# LaserCutter.net
KiCad netlist of a schematic drawn in EAGLE
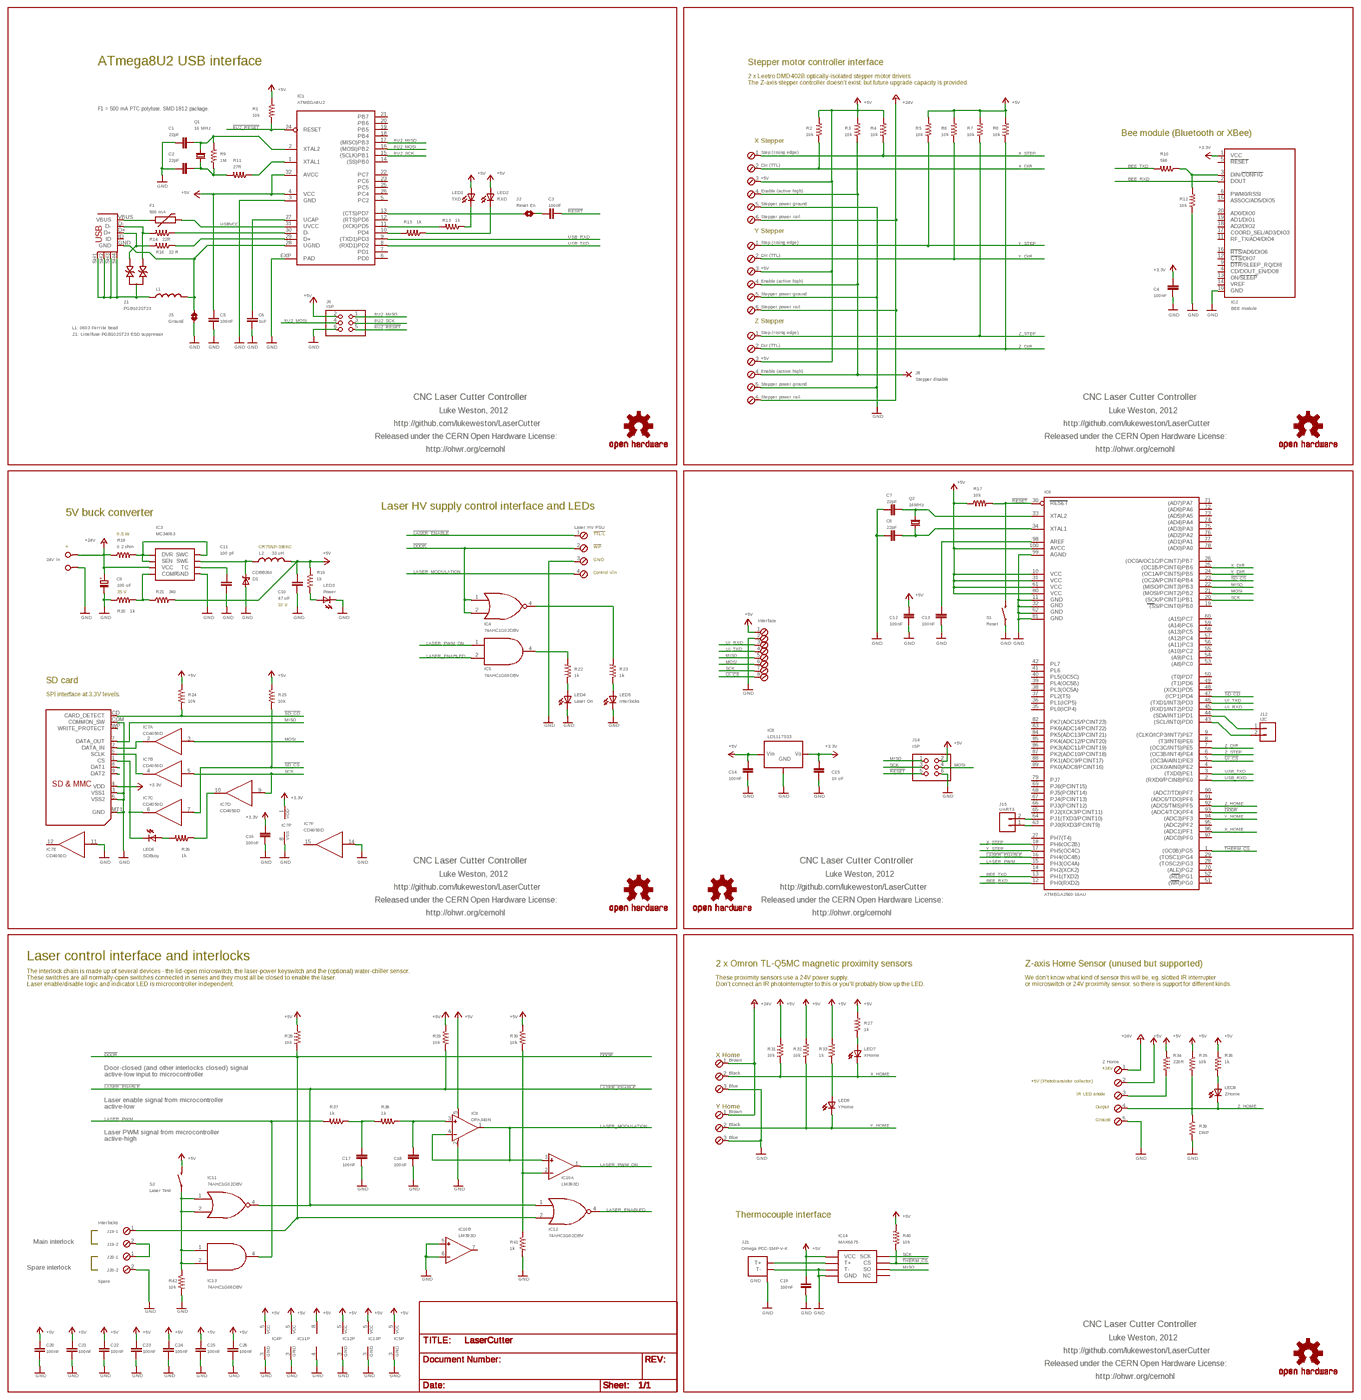
[diagram p0: schematic, sheet 1, overview]
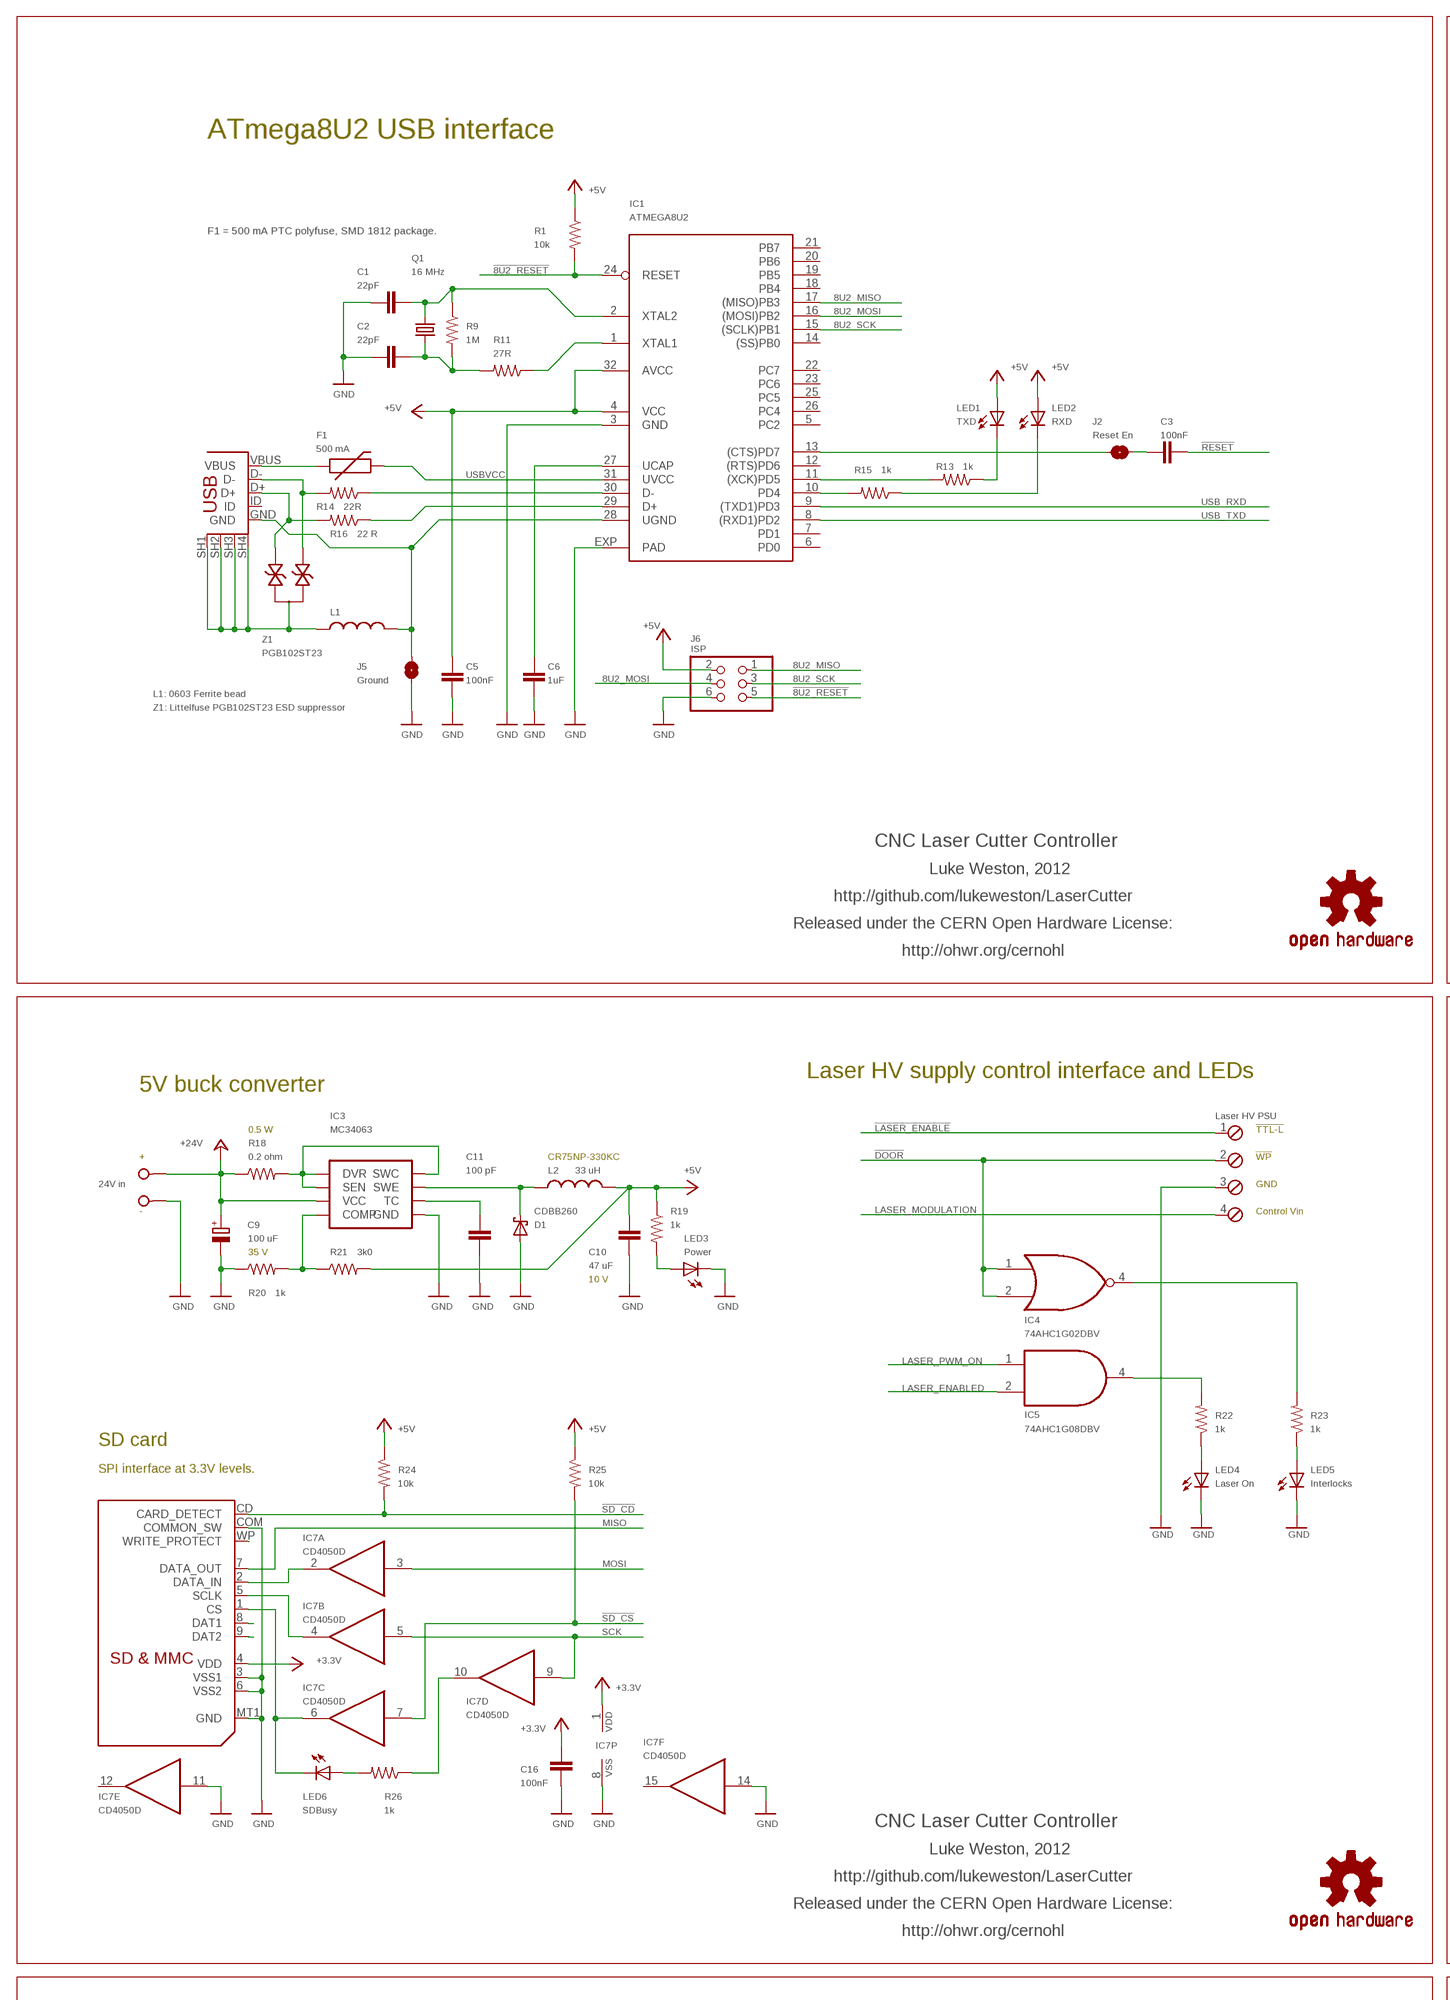
[diagram p1: schematic, sheet 1, part 1 of 4]
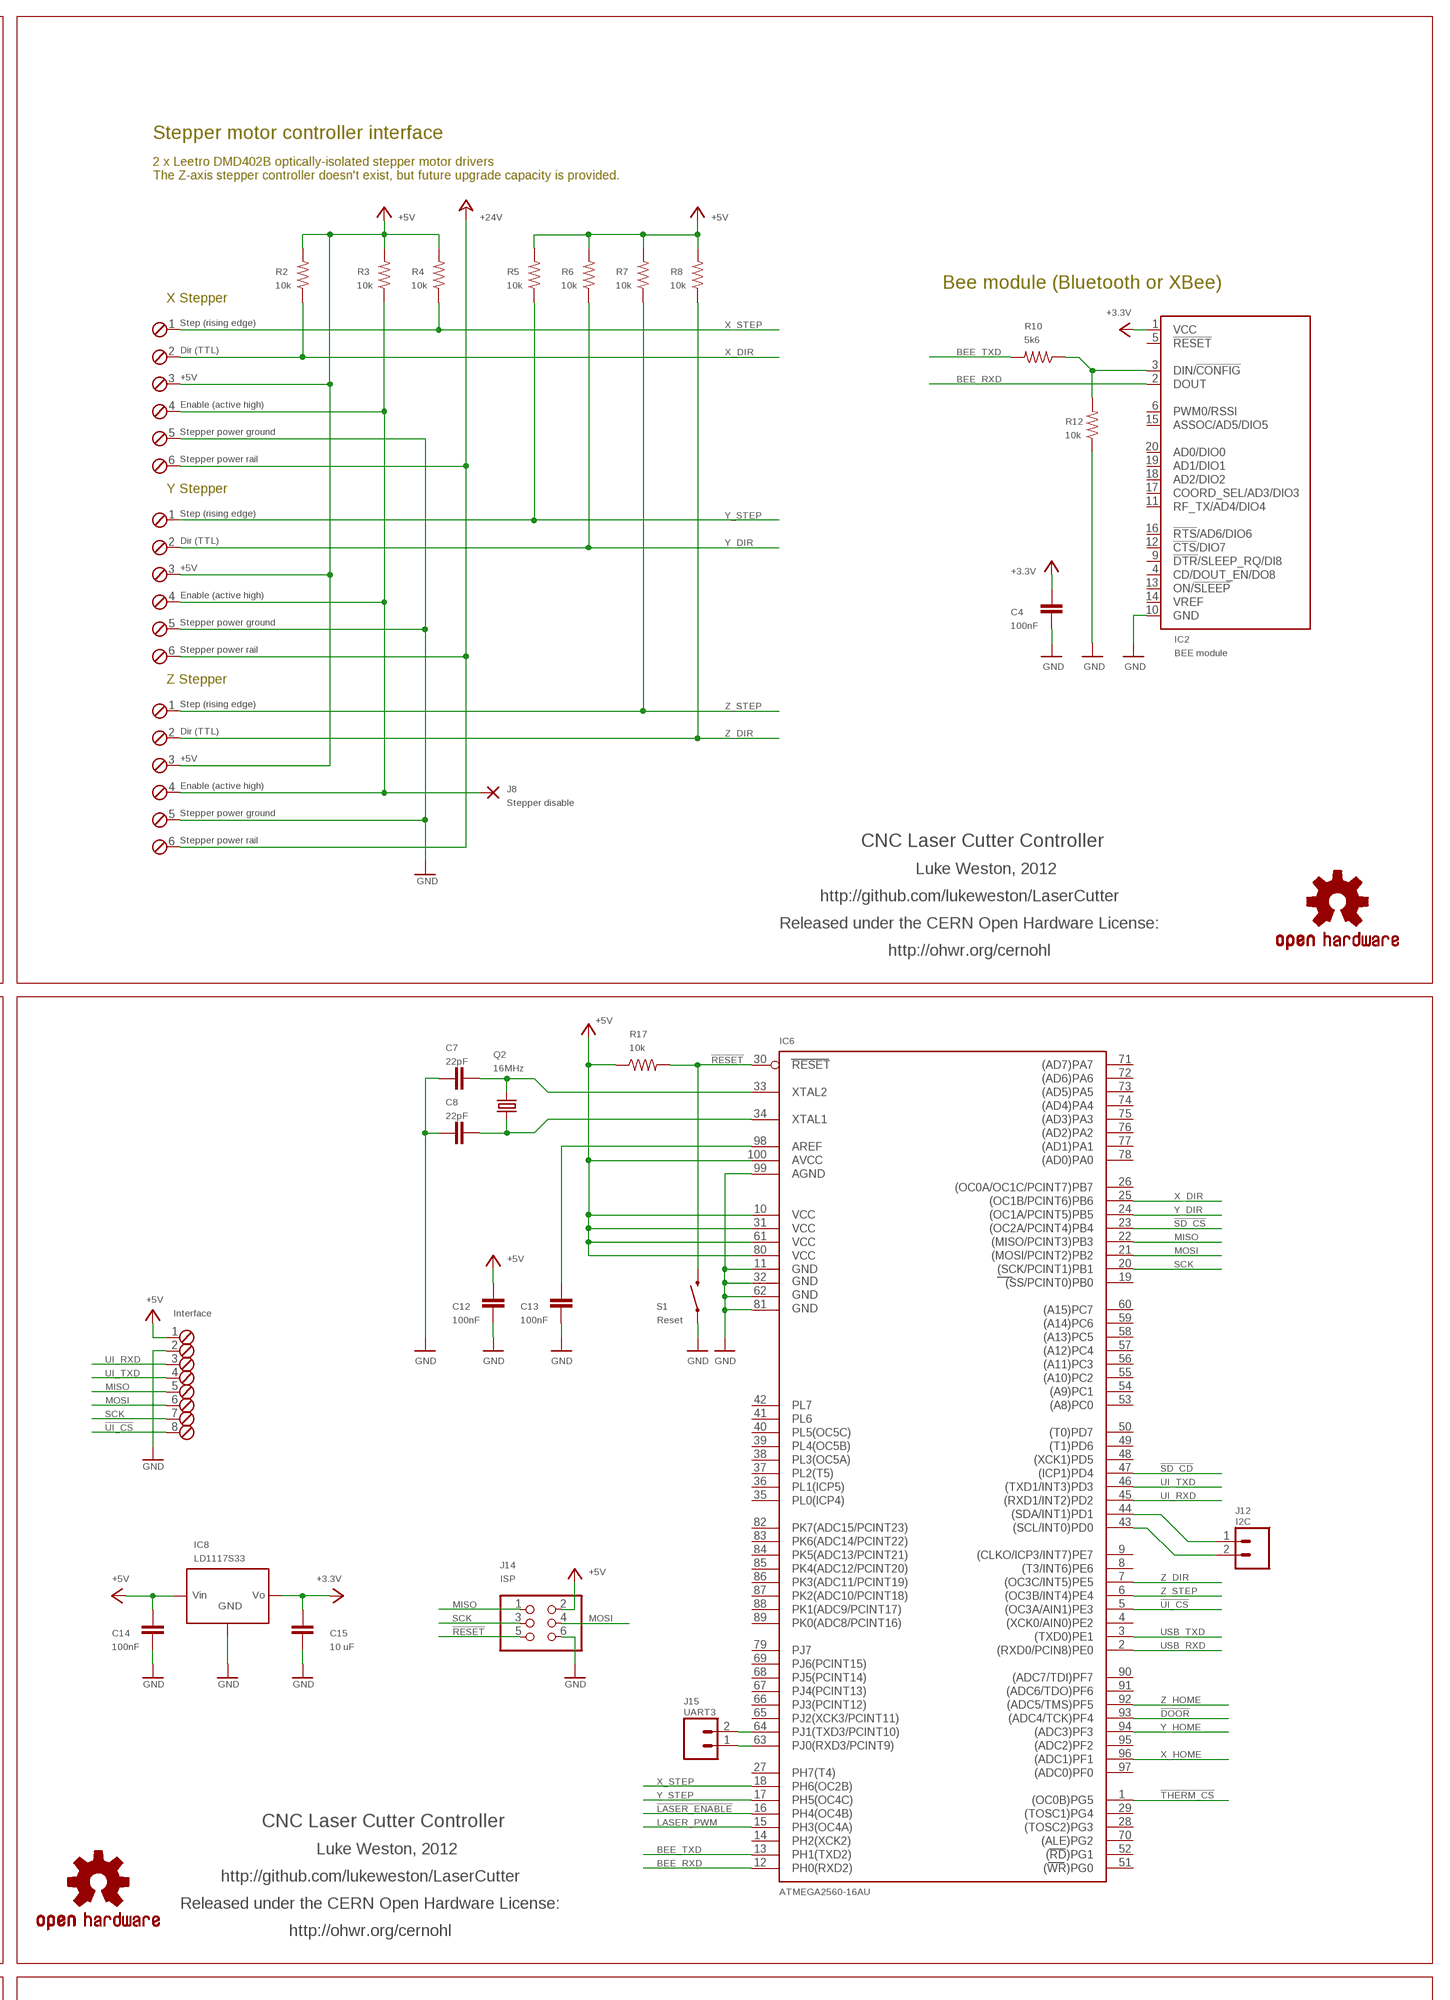
[diagram p2: schematic, sheet 1, part 2 of 4]
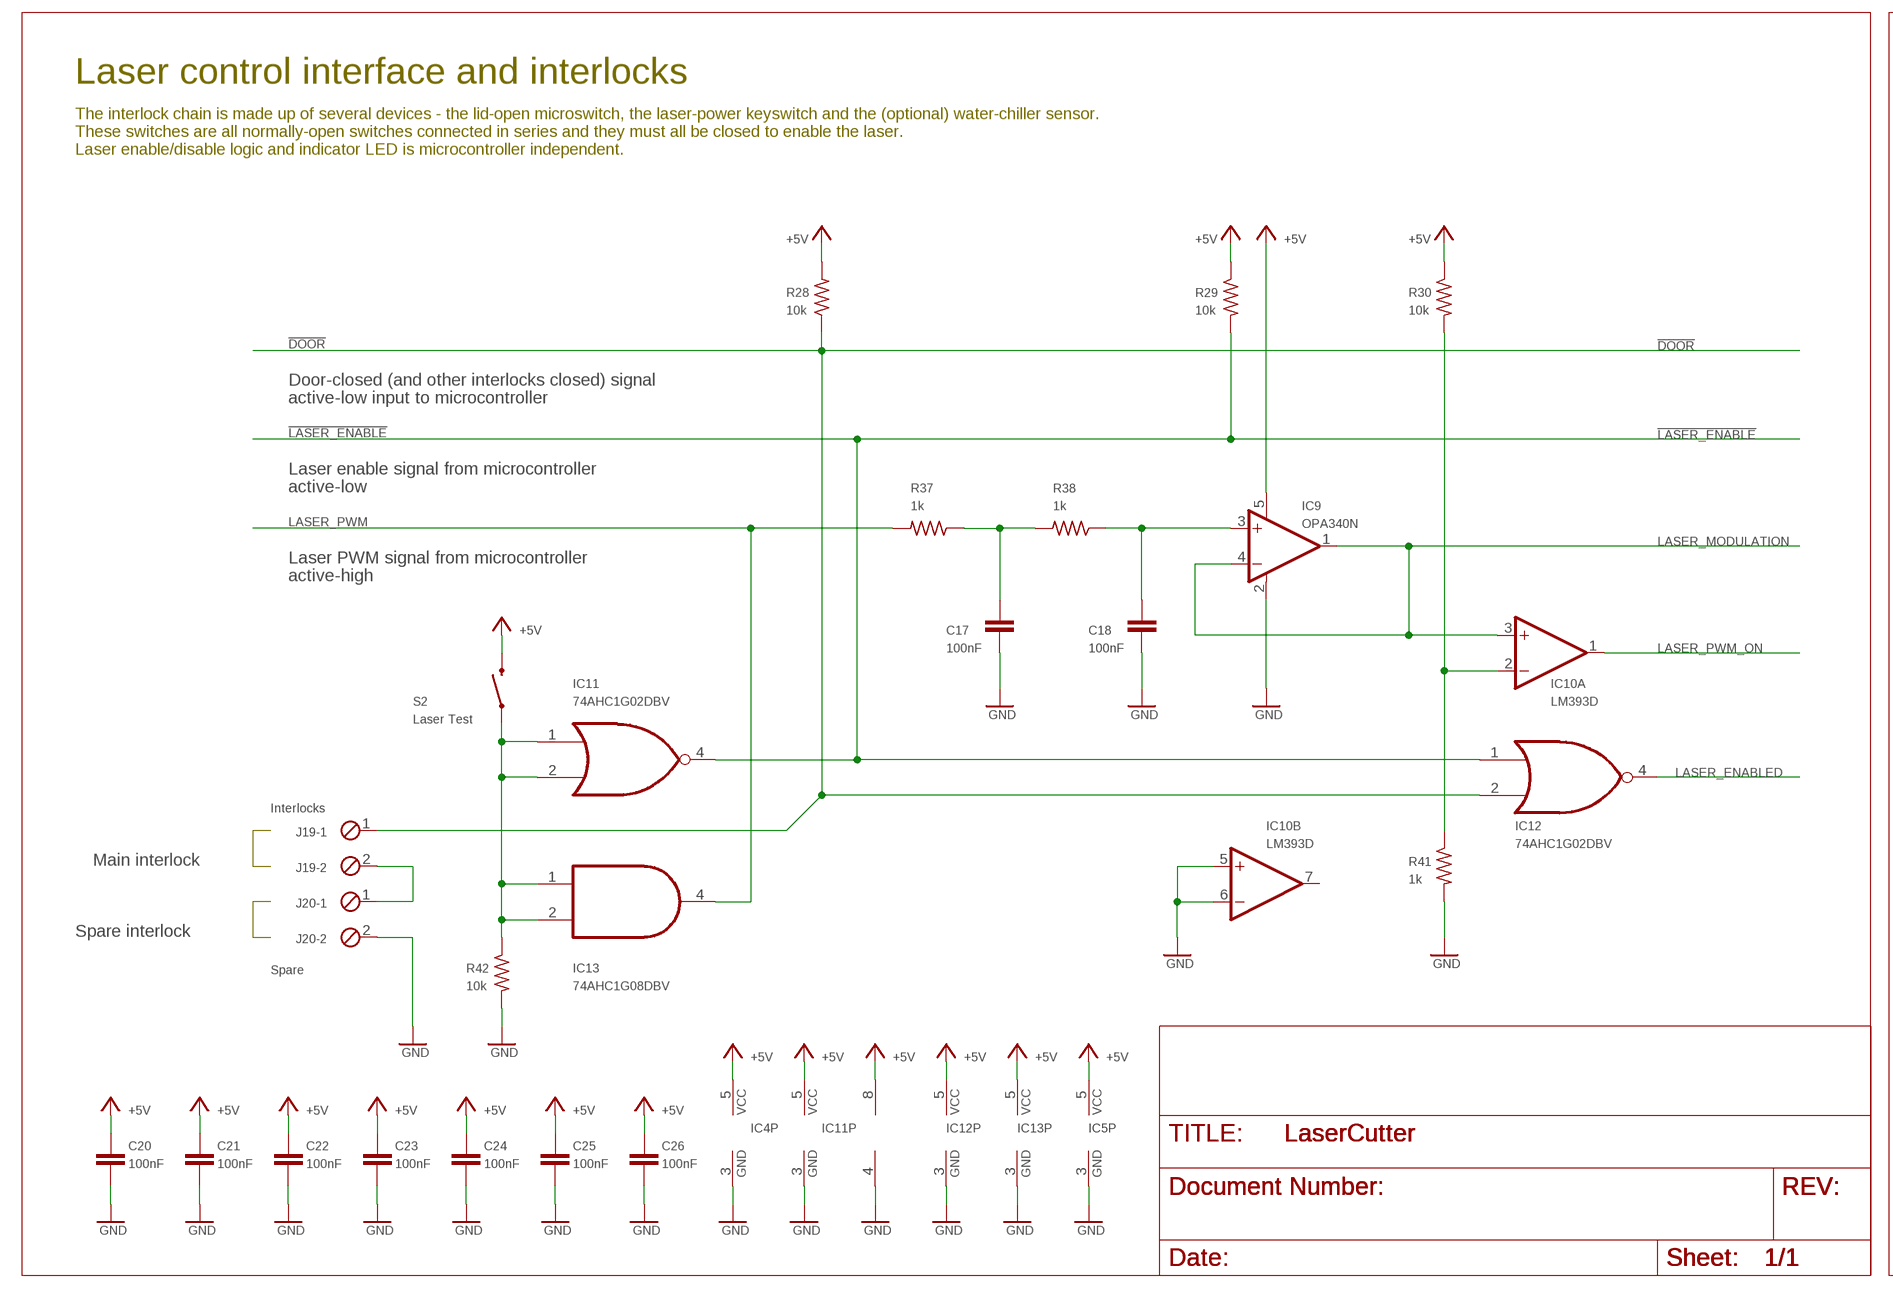
[diagram p3: schematic, sheet 1, part 3 of 4]
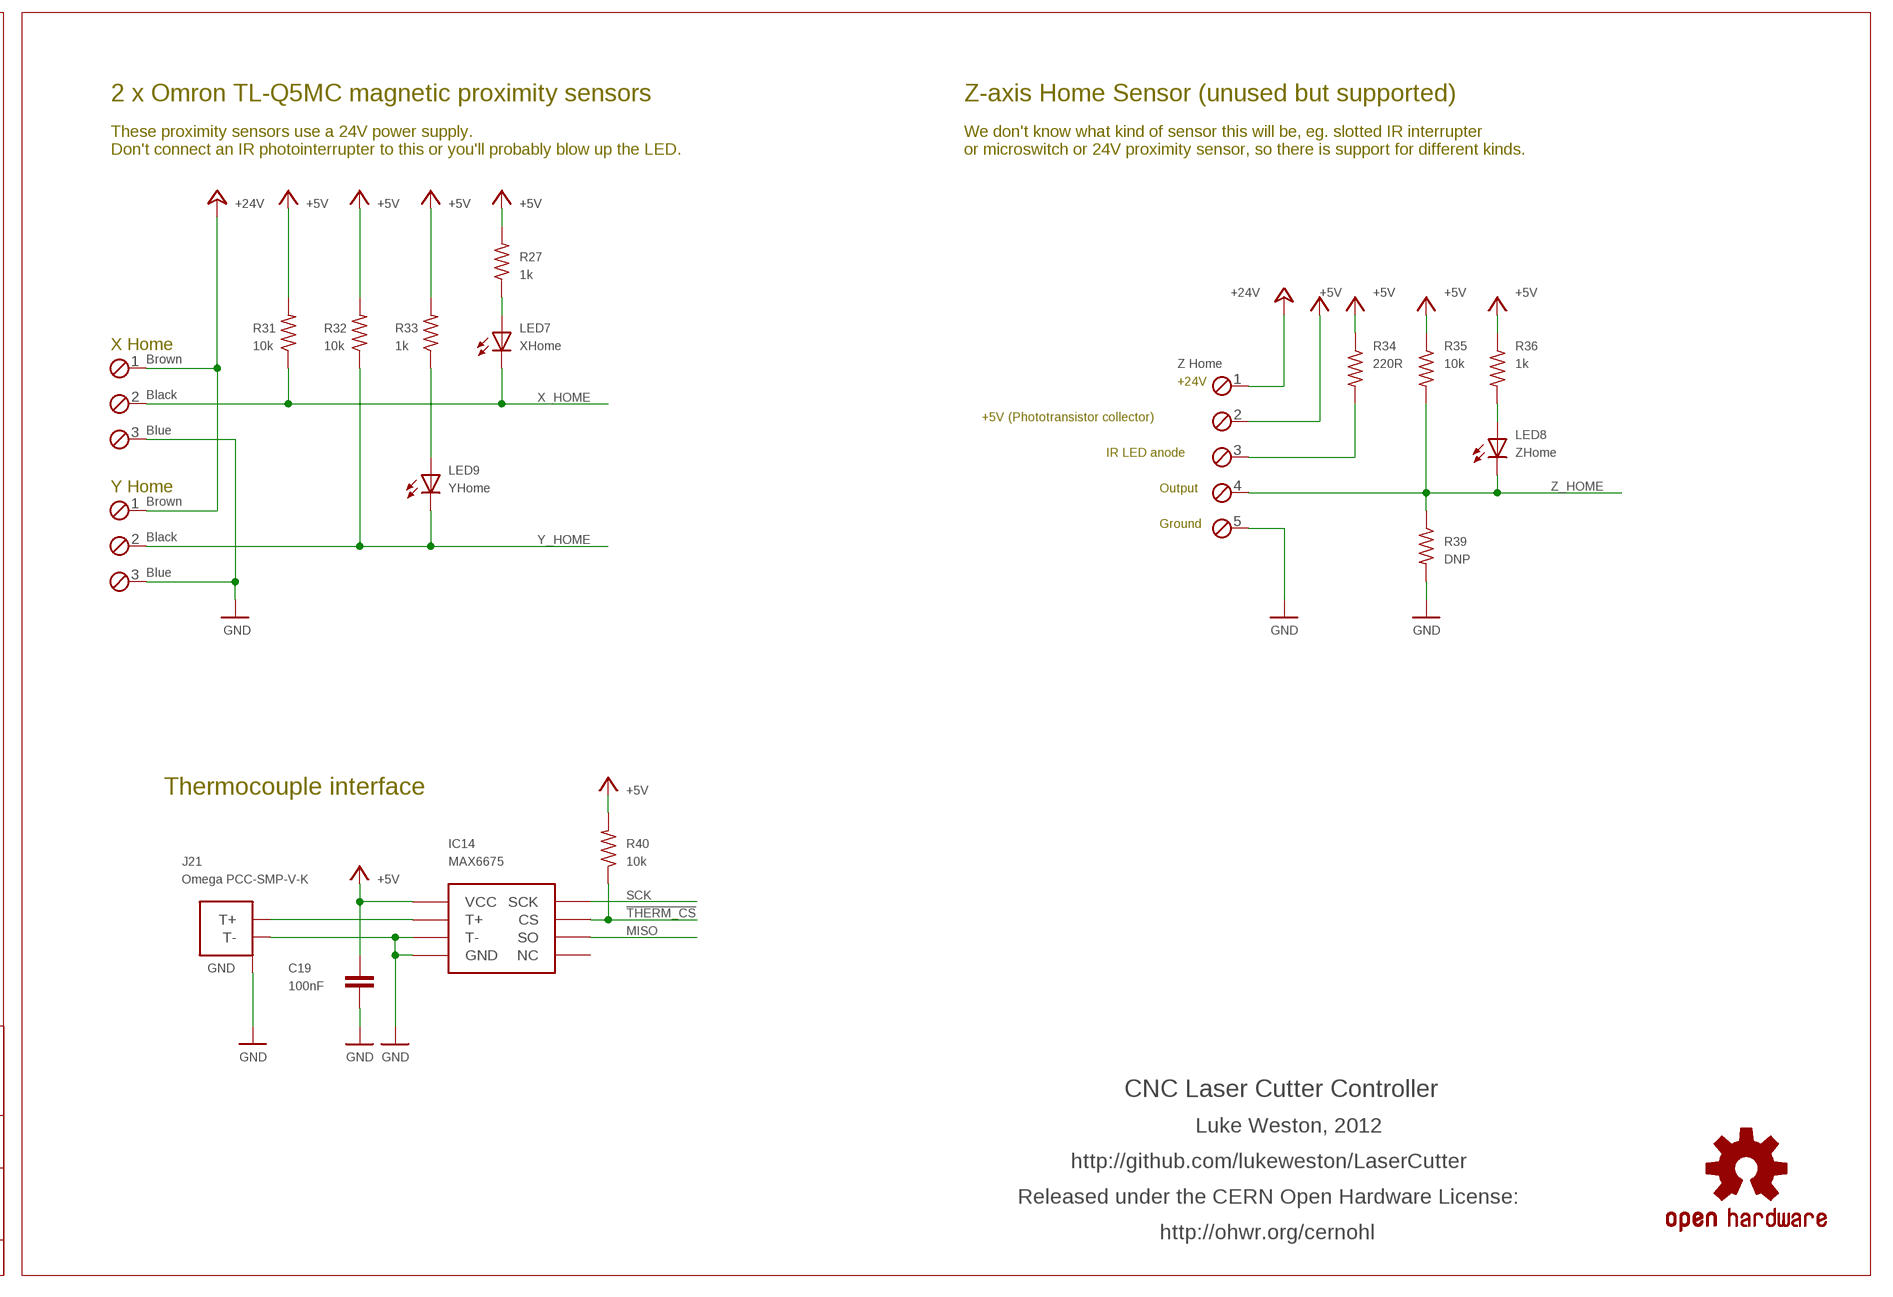
[diagram p4: schematic, sheet 1, part 4 of 4]

(export (version "E")
  (design (tool "Eeschema 10.0.6"))
  (components
    (comp (ref "$1")
      (value "OSHW-LOGOS")
      (footprint "eagle-import:OSHW-LOGO-S")
      (libsource (lib "eagle-import") (part "OSHW-LOGOS"))
    )
    (comp (ref "C1")
      (value "22pF")
      (footprint "eagle-import:0805-LARGE")
      (libsource (lib "eagle-import") (part "CAP0805-LARGE"))
    )
    (comp (ref "C2")
      (value "22pF")
      (footprint "eagle-import:0805-LARGE")
      (libsource (lib "eagle-import") (part "CAP0805-LARGE"))
    )
    (comp (ref "C3")
      (value "100nF")
      (footprint "eagle-import:0805-LARGE")
      (libsource (lib "eagle-import") (part "CAP0805-LARGE"))
    )
    (comp (ref "C4")
      (value "100nF")
      (footprint "eagle-import:C0805K")
      (libsource (lib "eagle-import") (part "C-EUC0805K"))
    )
    (comp (ref "C5")
      (value "100nF")
      (footprint "eagle-import:0805-LARGE")
      (libsource (lib "eagle-import") (part "CAP0805-LARGE"))
    )
    (comp (ref "C6")
      (value "1uF")
      (footprint "eagle-import:0805-LARGE")
      (libsource (lib "eagle-import") (part "freetronics-master-v1_CAP0805-LARGE"))
    )
    (comp (ref "C7")
      (value "22pF")
      (footprint "eagle-import:C0805K")
      (libsource (lib "eagle-import") (part "C-EUC0805K"))
    )
    (comp (ref "C8")
      (value "22pF")
      (footprint "eagle-import:C0805K")
      (libsource (lib "eagle-import") (part "C-EUC0805K"))
    )
    (comp (ref "C9")
      (value "100 uF")
      (footprint "eagle-import:E2,5-6")
      (libsource (lib "eagle-import") (part "CPOL-EUE2.5-6"))
    )
    (comp (ref "C10")
      (value "47 uF")
      (footprint "eagle-import:C1210")
      (libsource (lib "eagle-import") (part "C-EUC1210"))
    )
    (comp (ref "C11")
      (value "100 pF")
      (footprint "eagle-import:0805-LARGE")
      (libsource (lib "eagle-import") (part "freetronics-master-v1_CAP0805-LARGE"))
    )
    (comp (ref "C12")
      (value "100nF")
      (footprint "eagle-import:C0805K")
      (libsource (lib "eagle-import") (part "C-EUC0805K"))
    )
    (comp (ref "C13")
      (value "100nF")
      (footprint "eagle-import:C0805K")
      (libsource (lib "eagle-import") (part "C-EUC0805K"))
    )
    (comp (ref "C14")
      (value "100nF")
      (footprint "eagle-import:C0805K")
      (libsource (lib "eagle-import") (part "C-EUC0805K"))
    )
    (comp (ref "C15")
      (value "10 uF")
      (footprint "eagle-import:C0805K")
      (libsource (lib "eagle-import") (part "C-EUC0805K"))
    )
    (comp (ref "C16")
      (value "100nF")
      (footprint "eagle-import:C0805K")
      (libsource (lib "eagle-import") (part "C-EUC0805K"))
    )
    (comp (ref "C17")
      (value "100nF")
      (footprint "eagle-import:C0805K")
      (libsource (lib "eagle-import") (part "C-EUC0805K"))
    )
    (comp (ref "C18")
      (value "100nF")
      (footprint "eagle-import:C0805K")
      (libsource (lib "eagle-import") (part "C-EUC0805K"))
    )
    (comp (ref "C19")
      (value "100nF")
      (footprint "eagle-import:C0805K")
      (libsource (lib "eagle-import") (part "C-EUC0805K"))
    )
    (comp (ref "C20")
      (value "100nF")
      (footprint "eagle-import:C0805K")
      (libsource (lib "eagle-import") (part "C-EUC0805K"))
    )
    (comp (ref "C21")
      (value "100nF")
      (footprint "eagle-import:C0805K")
      (libsource (lib "eagle-import") (part "C-EUC0805K"))
    )
    (comp (ref "C22")
      (value "100nF")
      (footprint "eagle-import:C0805K")
      (libsource (lib "eagle-import") (part "C-EUC0805K"))
    )
    (comp (ref "C23")
      (value "100nF")
      (footprint "eagle-import:C0805K")
      (libsource (lib "eagle-import") (part "C-EUC0805K"))
    )
    (comp (ref "C24")
      (value "100nF")
      (footprint "eagle-import:C0805K")
      (libsource (lib "eagle-import") (part "C-EUC0805K"))
    )
    (comp (ref "C25")
      (value "100nF")
      (footprint "eagle-import:C0805K")
      (libsource (lib "eagle-import") (part "C-EUC0805K"))
    )
    (comp (ref "C26")
      (value "100nF")
      (footprint "eagle-import:C0805K")
      (libsource (lib "eagle-import") (part "C-EUC0805K"))
    )
    (comp (ref "D1")
      (value "CDBB260")
      (footprint "eagle-import:SMB")
      (libsource (lib "eagle-import") (part "MBRS130LT3"))
    )
    (comp (ref "F1")
      (value "500 mA")
      (footprint "eagle-import:1812")
      (libsource (lib "eagle-import") (part "PTC1812"))
    )
    (comp (ref "IC1")
      (value "ATMEGA8U2")
      (footprint "eagle-import:ATMEL_QFN32")
      (libsource (lib "eagle-import") (part "ATMEL_ATMEGA8U2-MUQFN"))
    )
    (comp (ref "IC2")
      (value "BEE module")
      (footprint "eagle-import:XBEE-PRO")
      (libsource (lib "eagle-import") (part "XBEE"))
    )
    (comp (ref "IC3")
      (value "MC34063")
      (footprint "eagle-import:SO08")
      (libsource (lib "eagle-import") (part "MC34063SMD"))
    )
    (comp (ref "IC4")
      (value "74AHC1G02DBV")
      (footprint "eagle-import:SOT23-5")
      (libsource (lib "eagle-import") (part "741G02DBVAHC"))
    )
    (comp (ref "IC5")
      (value "74AHC1G08DBV")
      (footprint "eagle-import:SOT23-5")
      (libsource (lib "eagle-import") (part "741G08DBVAHC"))
    )
    (comp (ref "IC6")
      (value "ATMEGA2560-16AU")
      (footprint "eagle-import:TQFP100")
      (libsource (lib "eagle-import") (part "ATMEGAAU1280-16"))
    )
    (comp (ref "IC7")
      (value "CD4050D")
      (footprint "eagle-import:SO16")
      (libsource (lib "eagle-import") (part "4050D"))
    )
    (comp (ref "IC8")
      (value "LD1117S33")
      (footprint "eagle-import:SOT223")
      (fields (field (name "MPN") "REG1117"))
      (libsource (lib "eagle-import") (part "REG1117"))
    )
    (comp (ref "IC9")
      (value "OPA340N")
      (footprint "eagle-import:SOT23-5")
      (fields (field (name "MPN") "OPA340NA/3KG4"))
      (libsource (lib "eagle-import") (part "OPA340N"))
    )
    (comp (ref "IC10")
      (value "LM393D")
      (footprint "eagle-import:SO08")
      (libsource (lib "eagle-import") (part "LM393D"))
    )
    (comp (ref "IC11")
      (value "74AHC1G02DBV")
      (footprint "eagle-import:SOT23-5")
      (libsource (lib "eagle-import") (part "741G02DBVAHC"))
    )
    (comp (ref "IC12")
      (value "74AHC1G02DBV")
      (footprint "eagle-import:SOT23-5")
      (libsource (lib "eagle-import") (part "741G02DBVAHC"))
    )
    (comp (ref "IC13")
      (value "74AHC1G08DBV")
      (footprint "eagle-import:SOT23-5")
      (libsource (lib "eagle-import") (part "741G08DBVAHC"))
    )
    (comp (ref "IC14")
      (value "MAX6675")
      (footprint "eagle-import:SOIC8-2")
      (libsource (lib "eagle-import") (part "MAX6675"))
    )
    (comp (ref "J1")
      (value "X Stepper")
      (footprint "eagle-import:6POL254")
      (libsource (lib "eagle-import") (part "MPT6"))
    )
    (comp (ref "J2")
      (value "Reset En")
      (footprint "eagle-import:SJ")
      (libsource (lib "eagle-import") (part "SJ"))
    )
    (comp (ref "J3")
      (value "USB")
      (footprint "eagle-import:USB-MINIB-FT")
      (libsource (lib "eagle-import") (part "USB-FT"))
    )
    (comp (ref "J4")
      (value "Y Stepper")
      (footprint "eagle-import:6POL254")
      (libsource (lib "eagle-import") (part "MPT6"))
    )
    (comp (ref "J5")
      (value "Ground")
      (footprint "eagle-import:SJ")
      (libsource (lib "eagle-import") (part "SJ"))
    )
    (comp (ref "J6")
      (value "ISP")
      (footprint "eagle-import:2X03")
      (libsource (lib "eagle-import") (part "PINHD-2X3"))
    )
    (comp (ref "J7")
      (value "Z Stepper")
      (footprint "eagle-import:6POL254")
      (libsource (lib "eagle-import") (part "MPT6"))
    )
    (comp (ref "J8")
      (value "Stepper disable")
      (footprint "eagle-import:1,6_0,8")
      (libsource (lib "eagle-import") (part "1,6/0,8"))
    )
    (comp (ref "J9")
      (value "Laser HV PSU")
      (footprint "eagle-import:4POL254")
      (libsource (lib "eagle-import") (part "MPT4"))
    )
    (comp (ref "J10")
      (value "24V in")
      (footprint "eagle-import:W237-132")
      (libsource (lib "eagle-import") (part "W237-02P"))
    )
    (comp (ref "J11")
      (value "Interface")
      (footprint "eagle-import:8POL254")
      (libsource (lib "eagle-import") (part "MPT8"))
    )
    (comp (ref "J12")
      (value "I2C")
      (footprint "eagle-import:1X02")
      (libsource (lib "eagle-import") (part "M02PTH"))
    )
    (comp (ref "J13")
      (value "SDMMC18650")
      (footprint "eagle-import:SDCARD")
      (libsource (lib "eagle-import") (part "SDMMC18650"))
    )
    (comp (ref "J14")
      (value "ISP")
      (footprint "eagle-import:2X03")
      (libsource (lib "eagle-import") (part "PINHD-2X3"))
    )
    (comp (ref "J15")
      (value "UART3")
      (footprint "eagle-import:1X02")
      (libsource (lib "eagle-import") (part "M02PTH"))
    )
    (comp (ref "J16")
      (value "X Home")
      (footprint "eagle-import:3POL254")
      (libsource (lib "eagle-import") (part "MPT3"))
    )
    (comp (ref "J17")
      (value "Z Home")
      (footprint "eagle-import:5POL254")
      (libsource (lib "eagle-import") (part "MPT5"))
    )
    (comp (ref "J18")
      (value "Y Home")
      (footprint "eagle-import:3POL254")
      (libsource (lib "eagle-import") (part "MPT3"))
    )
    (comp (ref "J19")
      (value "Interlocks")
      (footprint "eagle-import:2POL254")
      (libsource (lib "eagle-import") (part "MPT2"))
    )
    (comp (ref "J20")
      (value "Spare")
      (footprint "eagle-import:2POL254")
      (libsource (lib "eagle-import") (part "MPT2"))
    )
    (comp (ref "J21")
      (value "Omega PCC-SMP-V-K")
      (footprint "eagle-import:PCC-SMP-V")
      (libsource (lib "eagle-import") (part "PCC-SMP-V"))
    )
    (comp (ref "L1")
      (value "L1: 0603 Ferrite bead")
      (footprint "eagle-import:0603")
      (libsource (lib "eagle-import") (part "freetronics-master-v1_INDUCTOR0603"))
    )
    (comp (ref "L2")
      (value "33 uH")
      (footprint "eagle-import:CR75")
      (libsource (lib "eagle-import") (part "INDUCTORCR75"))
    )
    (comp (ref "LED1")
      (value "TXD")
      (footprint "eagle-import:LED-0805")
      (libsource (lib "eagle-import") (part "LED0805"))
    )
    (comp (ref "LED2")
      (value "RXD")
      (footprint "eagle-import:LED-0805")
      (libsource (lib "eagle-import") (part "LED0805"))
    )
    (comp (ref "LED3")
      (value "Power")
      (footprint "eagle-import:LED-0805-LARGE")
      (libsource (lib "eagle-import") (part "LED0805-LARGE"))
    )
    (comp (ref "LED4")
      (value "Laser On")
      (footprint "eagle-import:LED-0805-LARGE")
      (libsource (lib "eagle-import") (part "LED0805-LARGE"))
    )
    (comp (ref "LED5")
      (value "Interlocks")
      (footprint "eagle-import:LED-0805-LARGE")
      (libsource (lib "eagle-import") (part "LED0805-LARGE"))
    )
    (comp (ref "LED6")
      (value "SDBusy")
      (footprint "eagle-import:LED-0805-LARGE")
      (libsource (lib "eagle-import") (part "LED0805-LARGE"))
    )
    (comp (ref "LED7")
      (value "XHome")
      (footprint "eagle-import:LED-0805-LARGE")
      (libsource (lib "eagle-import") (part "LED0805-LARGE"))
    )
    (comp (ref "LED8")
      (value "ZHome")
      (footprint "eagle-import:LED-0805-LARGE")
      (libsource (lib "eagle-import") (part "LED0805-LARGE"))
    )
    (comp (ref "LED9")
      (value "YHome")
      (footprint "eagle-import:LED-0805-LARGE")
      (libsource (lib "eagle-import") (part "LED0805-LARGE"))
    )
    (comp (ref "Q1")
      (value "16 MHz")
      (footprint "eagle-import:CRYSTAL-SMD-5X3")
      (libsource (lib "eagle-import") (part "CRYSTAL5X3"))
    )
    (comp (ref "Q2")
      (value "16MHz")
      (footprint "eagle-import:CRYSTAL-SMD-5X3")
      (libsource (lib "eagle-import") (part "CRYSTAL5X3"))
    )
    (comp (ref "R1")
      (value "10k")
      (footprint "eagle-import:R0805")
      (libsource (lib "eagle-import") (part "R-US_R0805"))
    )
    (comp (ref "R2")
      (value "10k")
      (footprint "eagle-import:M0805")
      (libsource (lib "eagle-import") (part "resistor_R-US_M0805"))
    )
    (comp (ref "R3")
      (value "10k")
      (footprint "eagle-import:M0805")
      (libsource (lib "eagle-import") (part "resistor_R-US_M0805"))
    )
    (comp (ref "R4")
      (value "10k")
      (footprint "eagle-import:M0805")
      (libsource (lib "eagle-import") (part "resistor_R-US_M0805"))
    )
    (comp (ref "R5")
      (value "10k")
      (footprint "eagle-import:M0805")
      (libsource (lib "eagle-import") (part "resistor_R-US_M0805"))
    )
    (comp (ref "R6")
      (value "10k")
      (footprint "eagle-import:M0805")
      (libsource (lib "eagle-import") (part "resistor_R-US_M0805"))
    )
    (comp (ref "R7")
      (value "10k")
      (footprint "eagle-import:M0805")
      (libsource (lib "eagle-import") (part "resistor_R-US_M0805"))
    )
    (comp (ref "R8")
      (value "10k")
      (footprint "eagle-import:M0805")
      (libsource (lib "eagle-import") (part "resistor_R-US_M0805"))
    )
    (comp (ref "R9")
      (value "1M")
      (footprint "eagle-import:R0805")
      (libsource (lib "eagle-import") (part "R-US_R0805"))
    )
    (comp (ref "R10")
      (value "5k6")
      (footprint "eagle-import:M0805")
      (libsource (lib "eagle-import") (part "resistor_R-US_M0805"))
    )
    (comp (ref "R11")
      (value "27R")
      (footprint "eagle-import:R0805")
      (libsource (lib "eagle-import") (part "R-US_R0805"))
    )
    (comp (ref "R12")
      (value "10k")
      (footprint "eagle-import:M0805")
      (libsource (lib "eagle-import") (part "resistor_R-US_M0805"))
    )
    (comp (ref "R13")
      (value "1k")
      (footprint "eagle-import:R0805")
      (libsource (lib "eagle-import") (part "R-US_R0805"))
    )
    (comp (ref "R14")
      (value "22R")
      (footprint "eagle-import:R0805")
      (libsource (lib "eagle-import") (part "R-US_R0805"))
    )
    (comp (ref "R15")
      (value "1k")
      (footprint "eagle-import:R0805")
      (libsource (lib "eagle-import") (part "R-US_R0805"))
    )
    (comp (ref "R16")
      (value "22 R")
      (footprint "eagle-import:R0805")
      (libsource (lib "eagle-import") (part "R-US_R0805"))
    )
    (comp (ref "R17")
      (value "10k")
      (footprint "eagle-import:R0805")
      (libsource (lib "eagle-import") (part "R-US_R0805"))
    )
    (comp (ref "R18")
      (value "0.2 ohm")
      (footprint "eagle-import:R1210")
      (libsource (lib "eagle-import") (part "R-US_R1210"))
    )
    (comp (ref "R19")
      (value "1k")
      (footprint "eagle-import:R0805")
      (libsource (lib "eagle-import") (part "R-US_R0805"))
    )
    (comp (ref "R20")
      (value "1k")
      (footprint "eagle-import:R0805")
      (libsource (lib "eagle-import") (part "R-US_R0805"))
    )
    (comp (ref "R21")
      (value "3k0")
      (footprint "eagle-import:R0805")
      (libsource (lib "eagle-import") (part "R-US_R0805"))
    )
    (comp (ref "R22")
      (value "1k")
      (footprint "eagle-import:M0805")
      (libsource (lib "eagle-import") (part "resistor_R-US_M0805"))
    )
    (comp (ref "R23")
      (value "1k")
      (footprint "eagle-import:M0805")
      (libsource (lib "eagle-import") (part "resistor_R-US_M0805"))
    )
    (comp (ref "R24")
      (value "10k")
      (footprint "eagle-import:M0805")
      (libsource (lib "eagle-import") (part "resistor_R-US_M0805"))
    )
    (comp (ref "R25")
      (value "10k")
      (footprint "eagle-import:M0805")
      (libsource (lib "eagle-import") (part "resistor_R-US_M0805"))
    )
    (comp (ref "R26")
      (value "1k")
      (footprint "eagle-import:R0805")
      (libsource (lib "eagle-import") (part "R-US_R0805"))
    )
    (comp (ref "R27")
      (value "1k")
      (footprint "eagle-import:M0805")
      (libsource (lib "eagle-import") (part "resistor_R-US_M0805"))
    )
    (comp (ref "R28")
      (value "10k")
      (footprint "eagle-import:R0805")
      (libsource (lib "eagle-import") (part "resistor_R-US_R0805"))
    )
    (comp (ref "R29")
      (value "10k")
      (footprint "eagle-import:M0805")
      (libsource (lib "eagle-import") (part "resistor_R-US_M0805"))
    )
    (comp (ref "R30")
      (value "10k")
      (footprint "eagle-import:M0805")
      (libsource (lib "eagle-import") (part "resistor_R-US_M0805"))
    )
    (comp (ref "R31")
      (value "10k")
      (footprint "eagle-import:M0805")
      (libsource (lib "eagle-import") (part "resistor_R-US_M0805"))
    )
    (comp (ref "R32")
      (value "10k")
      (footprint "eagle-import:M0805")
      (libsource (lib "eagle-import") (part "resistor_R-US_M0805"))
    )
    (comp (ref "R33")
      (value "1k")
      (footprint "eagle-import:M0805")
      (libsource (lib "eagle-import") (part "resistor_R-US_M0805"))
    )
    (comp (ref "R34")
      (value "220R")
      (footprint "eagle-import:M0805")
      (libsource (lib "eagle-import") (part "resistor_R-US_M0805"))
    )
    (comp (ref "R35")
      (value "10k")
      (footprint "eagle-import:M0805")
      (libsource (lib "eagle-import") (part "resistor_R-US_M0805"))
    )
    (comp (ref "R36")
      (value "1k")
      (footprint "eagle-import:M0805")
      (libsource (lib "eagle-import") (part "resistor_R-US_M0805"))
    )
    (comp (ref "R37")
      (value "1k")
      (footprint "eagle-import:M0805")
      (libsource (lib "eagle-import") (part "resistor_R-US_M0805"))
    )
    (comp (ref "R38")
      (value "1k")
      (footprint "eagle-import:M0805")
      (libsource (lib "eagle-import") (part "resistor_R-US_M0805"))
    )
    (comp (ref "R39")
      (value "DNP")
      (footprint "eagle-import:M0805")
      (libsource (lib "eagle-import") (part "resistor_R-US_M0805"))
    )
    (comp (ref "R40")
      (value "10k")
      (footprint "eagle-import:M0805")
      (libsource (lib "eagle-import") (part "resistor_R-US_M0805"))
    )
    (comp (ref "R41")
      (value "1k")
      (footprint "eagle-import:M0805")
      (libsource (lib "eagle-import") (part "resistor_R-US_M0805"))
    )
    (comp (ref "R42")
      (value "10k")
      (footprint "eagle-import:M0805")
      (libsource (lib "eagle-import") (part "resistor_R-US_M0805"))
    )
    (comp (ref "S1")
      (value "Reset")
      (footprint "eagle-import:TACTILE_SWITCH_SMD")
      (libsource (lib "eagle-import") (part "SWITCH-MOMENTARY-2SMD"))
    )
    (comp (ref "S2")
      (value "Laser Test")
      (footprint "eagle-import:TACTILE_SWITCH_SMD")
      (libsource (lib "eagle-import") (part "SWITCH-MOMENTARY-2SMD"))
    )
    (comp (ref "U$")
      (value "OSHW-LOGOS")
      (footprint "eagle-import:OSHW-LOGO-S")
      (libsource (lib "eagle-import") (part "OSHW-LOGOS"))
    )
    (comp (ref "U$1")
      (value "OSHW-LOGOS")
      (footprint "eagle-import:OSHW-LOGO-S")
      (libsource (lib "eagle-import") (part "OSHW-LOGOS"))
    )
    (comp (ref "U$2")
      (value "OSHW-LOGOS")
      (footprint "eagle-import:OSHW-LOGO-S")
      (libsource (lib "eagle-import") (part "OSHW-LOGOS"))
    )
    (comp (ref "U$3")
      (value "OSHW-LOGOS")
      (footprint "eagle-import:OSHW-LOGO-S")
      (libsource (lib "eagle-import") (part "OSHW-LOGOS"))
    )
    (comp (ref "Z1")
      (value "PGB102ST23")
      (footprint "eagle-import:SOT23-3")
      (libsource (lib "eagle-import") (part "PGB102ST23"))
    )
  )
  (nets
    (net (code "1") (name "+3.3V") (class "Default")
      (node (ref "C15") (pin "1") (pinfunction "1_1") (pintype "passive"))
      (node (ref "C16") (pin "1") (pinfunction "1_1") (pintype "passive"))
      (node (ref "C4") (pin "1") (pinfunction "1_1") (pintype "passive"))
      (node (ref "IC2") (pin "1") (pinfunction "VCC_1") (pintype "power_in"))
      (node (ref "IC7") (pin "1") (pinfunction "VDD_1") (pintype "power_in"))
      (node (ref "IC8") (pin "2") (pinfunction "VOUT_2") (pintype "power_in"))
      (node (ref "J13") (pin "4") (pinfunction "VDD_4") (pintype "power_in"))
    )
    (net (code "2") (name "+5V") (class "Default")
      (node (ref "C10") (pin "1") (pinfunction "1_1") (pintype "passive"))
      (node (ref "C12") (pin "2") (pinfunction "2_2") (pintype "passive"))
      (node (ref "C14") (pin "1") (pinfunction "1_1") (pintype "passive"))
      (node (ref "C19") (pin "1") (pinfunction "1_1") (pintype "passive"))
      (node (ref "C20") (pin "1") (pinfunction "1_1") (pintype "passive"))
      (node (ref "C21") (pin "1") (pinfunction "1_1") (pintype "passive"))
      (node (ref "C22") (pin "1") (pinfunction "1_1") (pintype "passive"))
      (node (ref "C23") (pin "1") (pinfunction "1_1") (pintype "passive"))
      (node (ref "C24") (pin "1") (pinfunction "1_1") (pintype "passive"))
      (node (ref "C25") (pin "1") (pinfunction "1_1") (pintype "passive"))
      (node (ref "C26") (pin "1") (pinfunction "1_1") (pintype "passive"))
      (node (ref "C5") (pin "1") (pinfunction "1_1") (pintype "passive"))
      (node (ref "IC1") (pin "32") (pinfunction "AVCC_32") (pintype "power_in"))
      (node (ref "IC1") (pin "4") (pinfunction "VCC_4") (pintype "power_in"))
      (node (ref "IC10") (pin "8") (pinfunction "V+_8") (pintype "power_in"))
      (node (ref "IC11") (pin "5") (pinfunction "VCC_5") (pintype "power_in"))
      (node (ref "IC12") (pin "5") (pinfunction "VCC_5") (pintype "power_in"))
      (node (ref "IC13") (pin "5") (pinfunction "VCC_5") (pintype "power_in"))
      (node (ref "IC14") (pin "4") (pinfunction "VCC_4") (pintype "bidirectional"))
      (node (ref "IC4") (pin "5") (pinfunction "VCC_5") (pintype "power_in"))
      (node (ref "IC5") (pin "5") (pinfunction "VCC_5") (pintype "power_in"))
      (node (ref "IC6") (pin "10") (pinfunction "VCC_10") (pintype "power_in"))
      (node (ref "IC6") (pin "100") (pinfunction "AVCC_100") (pintype "power_in"))
      (node (ref "IC6") (pin "31") (pinfunction "VCC1_31") (pintype "power_in"))
      (node (ref "IC6") (pin "61") (pinfunction "VCC2_61") (pintype "power_in"))
      (node (ref "IC6") (pin "80") (pinfunction "VCC3_80") (pintype "power_in"))
      (node (ref "IC8") (pin "3") (pinfunction "VIN_3") (pintype "power_in"))
      (node (ref "IC9") (pin "5") (pinfunction "V+_5") (pintype "power_in"))
      (node (ref "J1") (pin "3") (pinfunction "1_3") (pintype "passive"))
      (node (ref "J11") (pin "1") (pinfunction "1_1") (pintype "passive"))
      (node (ref "J14") (pin "2") (pinfunction "2_2") (pintype "passive"))
      (node (ref "J17") (pin "2") (pinfunction "1_2") (pintype "passive"))
      (node (ref "J4") (pin "3") (pinfunction "1_3") (pintype "passive"))
      (node (ref "J6") (pin "2") (pinfunction "2_2") (pintype "passive"))
      (node (ref "J7") (pin "3") (pinfunction "1_3") (pintype "passive"))
      (node (ref "L2") (pin "P$2") (pinfunction "2_P$2") (pintype "passive"))
      (node (ref "LED1") (pin "A") (pinfunction "A_A") (pintype "passive"))
      (node (ref "LED2") (pin "A") (pinfunction "A_A") (pintype "passive"))
      (node (ref "R1") (pin "1") (pinfunction "1_1") (pintype "passive"))
      (node (ref "R17") (pin "1") (pinfunction "1_1") (pintype "passive"))
      (node (ref "R19") (pin "1") (pinfunction "1_1") (pintype "passive"))
      (node (ref "R2") (pin "2") (pinfunction "2_2") (pintype "passive"))
      (node (ref "R21") (pin "2") (pinfunction "2_2") (pintype "passive"))
      (node (ref "R24") (pin "1") (pinfunction "1_1") (pintype "passive"))
      (node (ref "R25") (pin "1") (pinfunction "1_1") (pintype "passive"))
      (node (ref "R27") (pin "2") (pinfunction "2_2") (pintype "passive"))
      (node (ref "R28") (pin "2") (pinfunction "2_2") (pintype "passive"))
      (node (ref "R29") (pin "1") (pinfunction "1_1") (pintype "passive"))
      (node (ref "R3") (pin "2") (pinfunction "2_2") (pintype "passive"))
      (node (ref "R30") (pin "1") (pinfunction "1_1") (pintype "passive"))
      (node (ref "R31") (pin "2") (pinfunction "2_2") (pintype "passive"))
      (node (ref "R32") (pin "2") (pinfunction "2_2") (pintype "passive"))
      (node (ref "R33") (pin "2") (pinfunction "2_2") (pintype "passive"))
      (node (ref "R34") (pin "1") (pinfunction "1_1") (pintype "passive"))
      (node (ref "R35") (pin "1") (pinfunction "1_1") (pintype "passive"))
      (node (ref "R36") (pin "1") (pinfunction "1_1") (pintype "passive"))
      (node (ref "R4") (pin "2") (pinfunction "2_2") (pintype "passive"))
      (node (ref "R40") (pin "2") (pinfunction "2_2") (pintype "passive"))
      (node (ref "R5") (pin "2") (pinfunction "2_2") (pintype "passive"))
      (node (ref "R6") (pin "2") (pinfunction "2_2") (pintype "passive"))
      (node (ref "R7") (pin "2") (pinfunction "2_2") (pintype "passive"))
      (node (ref "R8") (pin "2") (pinfunction "2_2") (pintype "passive"))
      (node (ref "S2") (pin "3") (pinfunction "2_3") (pintype "passive"))
    )
    (net (code "3") (name "+24V") (class "Default")
      (node (ref "C9") (pin "+") (pinfunction "+_+") (pintype "passive"))
      (node (ref "IC3") (pin "6") (pinfunction "VCC_6") (pintype "bidirectional"))
      (node (ref "J1") (pin "6") (pinfunction "1_6") (pintype "passive"))
      (node (ref "J10") (pin "1") (pinfunction "KL_1") (pintype "passive"))
      (node (ref "J16") (pin "1") (pinfunction "1_1") (pintype "passive"))
      (node (ref "J17") (pin "1") (pinfunction "1_1") (pintype "passive"))
      (node (ref "J18") (pin "1") (pinfunction "1_1") (pintype "passive"))
      (node (ref "J4") (pin "6") (pinfunction "1_6") (pintype "passive"))
      (node (ref "J7") (pin "6") (pinfunction "1_6") (pintype "passive"))
      (node (ref "R18") (pin "1") (pinfunction "1_1") (pintype "passive"))
    )
    (net (code "4") (name "/8U2_MISO") (class "Default")
      (node (ref "IC1") (pin "17") (pinfunction "(MISO)PB3_17") (pintype "bidirectional"))
      (node (ref "J6") (pin "1") (pinfunction "1_1") (pintype "passive"))
    )
    (net (code "5") (name "/8U2_MOSI") (class "Default")
      (node (ref "IC1") (pin "16") (pinfunction "(MOSI)PB2_16") (pintype "bidirectional"))
      (node (ref "J6") (pin "4") (pinfunction "4_4") (pintype "passive"))
    )
    (net (code "6") (name "/8U2_SCK") (class "Default")
      (node (ref "IC1") (pin "15") (pinfunction "(SCLK)PB1_15") (pintype "bidirectional"))
      (node (ref "J6") (pin "3") (pinfunction "3_3") (pintype "passive"))
    )
    (net (code "7") (name "/BEE_RXD") (class "Default")
      (node (ref "IC2") (pin "2") (pinfunction "DOUT_2") (pintype "output"))
      (node (ref "IC6") (pin "12") (pinfunction "PH0(RXD2)_12") (pintype "bidirectional"))
    )
    (net (code "8") (name "/BEE_TXD") (class "Default")
      (node (ref "IC6") (pin "13") (pinfunction "PH1(TXD2)_13") (pintype "bidirectional"))
      (node (ref "R10") (pin "2") (pinfunction "2_2") (pintype "passive"))
    )
    (net (code "9") (name "/LASER_ENABLED") (class "Default")
      (node (ref "IC12") (pin "4") (pinfunction "O_4") (pintype "output"))
      (node (ref "IC5") (pin "2") (pinfunction "I1_2") (pintype "input"))
    )
    (net (code "10") (name "/LASER_MODULATION") (class "Default")
      (node (ref "IC10") (pin "3") (pinfunction "+IN_3") (pintype "input"))
      (node (ref "IC9") (pin "1") (pinfunction "OUT_1") (pintype "output"))
      (node (ref "IC9") (pin "4") (pinfunction "-IN_4") (pintype "input"))
      (node (ref "J9") (pin "4") (pinfunction "1_4") (pintype "passive"))
    )
    (net (code "11") (name "/LASER_PWM") (class "Default")
      (node (ref "IC13") (pin "4") (pinfunction "O_4") (pintype "output"))
      (node (ref "IC6") (pin "15") (pinfunction "PH3(OC4A)_15") (pintype "bidirectional"))
      (node (ref "R37") (pin "2") (pinfunction "2_2") (pintype "passive"))
    )
    (net (code "12") (name "/LASER_PWM_ON") (class "Default")
      (node (ref "IC10") (pin "1") (pinfunction "OUT_1") (pintype "output"))
      (node (ref "IC5") (pin "1") (pinfunction "I0_1") (pintype "input"))
    )
    (net (code "13") (name "/MISO") (class "Default")
      (node (ref "IC14") (pin "7") (pinfunction "SO_7") (pintype "bidirectional"))
      (node (ref "IC6") (pin "22") (pinfunction "(MISO/PCINT3)PB3_22") (pintype "bidirectional"))
      (node (ref "J11") (pin "5") (pinfunction "1_5") (pintype "passive"))
      (node (ref "J13") (pin "7") (pinfunction "DATA_OUT_7") (pintype "output"))
      (node (ref "J14") (pin "1") (pinfunction "1_1") (pintype "passive"))
    )
    (net (code "14") (name "/MOSI") (class "Default")
      (node (ref "IC6") (pin "21") (pinfunction "(MOSI/PCINT2)PB2_21") (pintype "bidirectional"))
      (node (ref "IC7") (pin "3") (pinfunction "I_3") (pintype "input"))
      (node (ref "J11") (pin "6") (pinfunction "1_6") (pintype "passive"))
      (node (ref "J14") (pin "4") (pinfunction "4_4") (pintype "passive"))
    )
    (net (code "15") (name "/SCK") (class "Default")
      (node (ref "IC14") (pin "5") (pinfunction "SCK_5") (pintype "bidirectional"))
      (node (ref "IC6") (pin "20") (pinfunction "(SCK/PCINT1)PB1_20") (pintype "bidirectional"))
      (node (ref "IC7") (pin "5") (pinfunction "I_5") (pintype "input"))
      (node (ref "IC7") (pin "9") (pinfunction "I_9") (pintype "input"))
      (node (ref "J11") (pin "7") (pinfunction "1_7") (pintype "passive"))
      (node (ref "J14") (pin "3") (pinfunction "3_3") (pintype "passive"))
    )
    (net (code "16") (name "/UI_RXD") (class "Default")
      (node (ref "IC6") (pin "45") (pinfunction "(RXD1/INT2)PD2_45") (pintype "bidirectional"))
      (node (ref "J11") (pin "3") (pinfunction "1_3") (pintype "passive"))
    )
    (net (code "17") (name "/UI_TXD") (class "Default")
      (node (ref "IC6") (pin "46") (pinfunction "(TXD1/INT3)PD3_46") (pintype "bidirectional"))
      (node (ref "J11") (pin "4") (pinfunction "1_4") (pintype "passive"))
    )
    (net (code "18") (name "/USBVCC") (class "Default")
      (node (ref "F1") (pin "2") (pinfunction "2_2") (pintype "bidirectional"))
      (node (ref "IC1") (pin "31") (pinfunction "UVCC_31") (pintype "power_in"))
    )
    (net (code "19") (name "/USB_RXD") (class "Default")
      (node (ref "IC1") (pin "9") (pinfunction "(TXD1)PD3_9") (pintype "bidirectional"))
      (node (ref "IC6") (pin "2") (pinfunction "(RXD0/PCIN8)PE0_2") (pintype "bidirectional"))
    )
    (net (code "20") (name "/USB_TXD") (class "Default")
      (node (ref "IC1") (pin "8") (pinfunction "(RXD1)PD2_8") (pintype "bidirectional"))
      (node (ref "IC6") (pin "3") (pinfunction "(TXD0)PE1_3") (pintype "bidirectional"))
    )
    (net (code "21") (name "/X_DIR") (class "Default")
      (node (ref "IC6") (pin "25") (pinfunction "(OC1B/PCINT6)PB6_25") (pintype "bidirectional"))
      (node (ref "J1") (pin "2") (pinfunction "1_2") (pintype "passive"))
      (node (ref "R2") (pin "1") (pinfunction "1_1") (pintype "passive"))
    )
    (net (code "22") (name "/X_HOME") (class "Default")
      (node (ref "IC6") (pin "96") (pinfunction "(ADC1)PF1_96") (pintype "bidirectional"))
      (node (ref "J16") (pin "2") (pinfunction "1_2") (pintype "passive"))
      (node (ref "LED7") (pin "C") (pinfunction "C_C") (pintype "passive"))
      (node (ref "R31") (pin "1") (pinfunction "1_1") (pintype "passive"))
    )
    (net (code "23") (name "/X_STEP") (class "Default")
      (node (ref "IC6") (pin "18") (pinfunction "PH6(OC2B)_18") (pintype "bidirectional"))
      (node (ref "J1") (pin "1") (pinfunction "1_1") (pintype "passive"))
      (node (ref "R4") (pin "1") (pinfunction "1_1") (pintype "passive"))
    )
    (net (code "24") (name "/Y_DIR") (class "Default")
      (node (ref "IC6") (pin "24") (pinfunction "(OC1A/PCINT5)PB5_24") (pintype "bidirectional"))
      (node (ref "J4") (pin "2") (pinfunction "1_2") (pintype "passive"))
      (node (ref "R6") (pin "1") (pinfunction "1_1") (pintype "passive"))
    )
    (net (code "25") (name "/Y_HOME") (class "Default")
      (node (ref "IC6") (pin "94") (pinfunction "(ADC3)PF3_94") (pintype "bidirectional"))
      (node (ref "J18") (pin "2") (pinfunction "1_2") (pintype "passive"))
      (node (ref "LED9") (pin "C") (pinfunction "C_C") (pintype "passive"))
      (node (ref "R32") (pin "1") (pinfunction "1_1") (pintype "passive"))
    )
    (net (code "26") (name "/Y_STEP") (class "Default")
      (node (ref "IC6") (pin "17") (pinfunction "PH5(OC4C)_17") (pintype "bidirectional"))
      (node (ref "J4") (pin "1") (pinfunction "1_1") (pintype "passive"))
      (node (ref "R5") (pin "1") (pinfunction "1_1") (pintype "passive"))
    )
    (net (code "27") (name "/Z_DIR") (class "Default")
      (node (ref "IC6") (pin "7") (pinfunction "(OC3C/INT5)PE5_7") (pintype "bidirectional"))
      (node (ref "J7") (pin "2") (pinfunction "1_2") (pintype "passive"))
      (node (ref "R8") (pin "1") (pinfunction "1_1") (pintype "passive"))
    )
    (net (code "28") (name "/Z_HOME") (class "Default")
      (node (ref "IC6") (pin "92") (pinfunction "(ADC5/TMS)PF5_92") (pintype "bidirectional"))
      (node (ref "J17") (pin "4") (pinfunction "1_4") (pintype "passive"))
      (node (ref "LED8") (pin "C") (pinfunction "C_C") (pintype "passive"))
      (node (ref "R35") (pin "2") (pinfunction "2_2") (pintype "passive"))
      (node (ref "R39") (pin "1") (pinfunction "1_1") (pintype "passive"))
    )
    (net (code "29") (name "/Z_STEP") (class "Default")
      (node (ref "IC6") (pin "6") (pinfunction "(OC3B/INT4)PE4_6") (pintype "bidirectional"))
      (node (ref "J7") (pin "1") (pinfunction "1_1") (pintype "passive"))
      (node (ref "R7") (pin "1") (pinfunction "1_1") (pintype "passive"))
    )
    (net (code "30") (name "/~{8U2_RESET}") (class "Default")
      (node (ref "IC1") (pin "24") (pinfunction "RESET_24") (pintype "input"))
      (node (ref "J6") (pin "5") (pinfunction "5_5") (pintype "passive"))
      (node (ref "R1") (pin "2") (pinfunction "2_2") (pintype "passive"))
    )
    (net (code "31") (name "/~{DOOR}") (class "Default")
      (node (ref "IC12") (pin "2") (pinfunction "I1_2") (pintype "input"))
      (node (ref "IC4") (pin "1") (pinfunction "I0_1") (pintype "input"))
      (node (ref "IC4") (pin "2") (pinfunction "I1_2") (pintype "input"))
      (node (ref "IC6") (pin "93") (pinfunction "(ADC4/TCK)PF4_93") (pintype "bidirectional"))
      (node (ref "J19") (pin "1") (pinfunction "1_1") (pintype "passive"))
      (node (ref "J9") (pin "2") (pinfunction "1_2") (pintype "passive"))
      (node (ref "R28") (pin "1") (pinfunction "1_1") (pintype "passive"))
    )
    (net (code "32") (name "/~{LASER_ENABLE}") (class "Default")
      (node (ref "IC11") (pin "4") (pinfunction "O_4") (pintype "output"))
      (node (ref "IC12") (pin "1") (pinfunction "I0_1") (pintype "input"))
      (node (ref "IC6") (pin "16") (pinfunction "PH4(OC4B)_16") (pintype "bidirectional"))
      (node (ref "J9") (pin "1") (pinfunction "1_1") (pintype "passive"))
      (node (ref "R29") (pin "2") (pinfunction "2_2") (pintype "passive"))
    )
    (net (code "33") (name "/~{RESET}") (class "Default")
      (node (ref "C3") (pin "2") (pinfunction "2_2") (pintype "passive"))
      (node (ref "IC6") (pin "30") (pinfunction "RESET_30") (pintype "input"))
      (node (ref "J14") (pin "5") (pinfunction "5_5") (pintype "passive"))
      (node (ref "R17") (pin "2") (pinfunction "2_2") (pintype "passive"))
      (node (ref "S1") (pin "3") (pinfunction "2_3") (pintype "passive"))
    )
    (net (code "34") (name "/~{SD_CD}") (class "Default")
      (node (ref "IC6") (pin "47") (pinfunction "(ICP1)PD4_47") (pintype "bidirectional"))
      (node (ref "J13") (pin "CD") (pinfunction "CARD_DETECT_CD") (pintype "passive"))
      (node (ref "R24") (pin "2") (pinfunction "2_2") (pintype "passive"))
    )
    (net (code "35") (name "/~{SD_CS}") (class "Default")
      (node (ref "IC6") (pin "23") (pinfunction "(OC2A/PCINT4)PB4_23") (pintype "bidirectional"))
      (node (ref "IC7") (pin "7") (pinfunction "I_7") (pintype "input"))
      (node (ref "R25") (pin "2") (pinfunction "2_2") (pintype "passive"))
    )
    (net (code "36") (name "/~{THERM_CS}") (class "Default")
      (node (ref "IC14") (pin "6") (pinfunction "CS_6") (pintype "bidirectional"))
      (node (ref "IC6") (pin "1") (pinfunction "(OC0B)PG5_1") (pintype "bidirectional"))
      (node (ref "R40") (pin "1") (pinfunction "1_1") (pintype "passive"))
    )
    (net (code "37") (name "/~{UI_CS}") (class "Default")
      (node (ref "IC6") (pin "5") (pinfunction "(OC3A/AIN1)PE3_5") (pintype "bidirectional"))
      (node (ref "J11") (pin "8") (pinfunction "1_8") (pintype "passive"))
    )
    (net (code "38") (name "GND") (class "Default")
      (node (ref "C1") (pin "1") (pinfunction "1_1") (pintype "passive"))
      (node (ref "C10") (pin "2") (pinfunction "2_2") (pintype "passive"))
      (node (ref "C11") (pin "2") (pinfunction "2_2") (pintype "passive"))
      (node (ref "C12") (pin "1") (pinfunction "1_1") (pintype "passive"))
      (node (ref "C13") (pin "1") (pinfunction "1_1") (pintype "passive"))
      (node (ref "C14") (pin "2") (pinfunction "2_2") (pintype "passive"))
      (node (ref "C15") (pin "2") (pinfunction "2_2") (pintype "passive"))
      (node (ref "C16") (pin "2") (pinfunction "2_2") (pintype "passive"))
      (node (ref "C17") (pin "2") (pinfunction "2_2") (pintype "passive"))
      (node (ref "C18") (pin "2") (pinfunction "2_2") (pintype "passive"))
      (node (ref "C19") (pin "2") (pinfunction "2_2") (pintype "passive"))
      (node (ref "C2") (pin "1") (pinfunction "1_1") (pintype "passive"))
      (node (ref "C20") (pin "2") (pinfunction "2_2") (pintype "passive"))
      (node (ref "C21") (pin "2") (pinfunction "2_2") (pintype "passive"))
      (node (ref "C22") (pin "2") (pinfunction "2_2") (pintype "passive"))
      (node (ref "C23") (pin "2") (pinfunction "2_2") (pintype "passive"))
      (node (ref "C24") (pin "2") (pinfunction "2_2") (pintype "passive"))
      (node (ref "C25") (pin "2") (pinfunction "2_2") (pintype "passive"))
      (node (ref "C26") (pin "2") (pinfunction "2_2") (pintype "passive"))
      (node (ref "C4") (pin "2") (pinfunction "2_2") (pintype "passive"))
      (node (ref "C5") (pin "2") (pinfunction "2_2") (pintype "passive"))
      (node (ref "C6") (pin "2") (pinfunction "2_2") (pintype "passive"))
      (node (ref "C7") (pin "1") (pinfunction "1_1") (pintype "passive"))
      (node (ref "C8") (pin "1") (pinfunction "1_1") (pintype "passive"))
      (node (ref "C9") (pin "-") (pinfunction "-_-") (pintype "passive"))
      (node (ref "D1") (pin "A") (pinfunction "A_A") (pintype "passive"))
      (node (ref "IC1") (pin "3") (pinfunction "GND_3") (pintype "power_in"))
      (node (ref "IC1") (pin "EXP") (pinfunction "PAD_EXP") (pintype "power_in"))
      (node (ref "IC10") (pin "4") (pinfunction "V-_4") (pintype "power_in"))
      (node (ref "IC10") (pin "5") (pinfunction "+IN_5") (pintype "input"))
      (node (ref "IC10") (pin "6") (pinfunction "-IN_6") (pintype "input"))
      (node (ref "IC11") (pin "3") (pinfunction "GND_3") (pintype "power_in"))
      (node (ref "IC12") (pin "3") (pinfunction "GND_3") (pintype "power_in"))
      (node (ref "IC13") (pin "3") (pinfunction "GND_3") (pintype "power_in"))
      (node (ref "IC14") (pin "1") (pinfunction "GND_1") (pintype "bidirectional"))
      (node (ref "IC14") (pin "2") (pinfunction "T-_2") (pintype "bidirectional"))
      (node (ref "IC2") (pin "10") (pinfunction "GND_10") (pintype "power_in"))
      (node (ref "IC3") (pin "4") (pinfunction "GND_4") (pintype "bidirectional"))
      (node (ref "IC4") (pin "3") (pinfunction "GND_3") (pintype "power_in"))
      (node (ref "IC5") (pin "3") (pinfunction "GND_3") (pintype "power_in"))
      (node (ref "IC6") (pin "11") (pinfunction "GND_11") (pintype "power_in"))
      (node (ref "IC6") (pin "32") (pinfunction "GND1_32") (pintype "power_in"))
      (node (ref "IC6") (pin "62") (pinfunction "GND2_62") (pintype "power_in"))
      (node (ref "IC6") (pin "81") (pinfunction "GND3_81") (pintype "power_in"))
      (node (ref "IC6") (pin "99") (pinfunction "AGND_99") (pintype "power_in"))
      (node (ref "IC7") (pin "11") (pinfunction "I_11") (pintype "input"))
      (node (ref "IC7") (pin "14") (pinfunction "I_14") (pintype "input"))
      (node (ref "IC7") (pin "8") (pinfunction "VSS_8") (pintype "power_in"))
      (node (ref "IC8") (pin "1") (pinfunction "GND_1") (pintype "power_in"))
      (node (ref "IC9") (pin "2") (pinfunction "V-_2") (pintype "power_in"))
      (node (ref "J1") (pin "5") (pinfunction "1_5") (pintype "passive"))
      (node (ref "J10") (pin "2") (pinfunction "KL_2") (pintype "passive"))
      (node (ref "J11") (pin "2") (pinfunction "1_2") (pintype "passive"))
      (node (ref "J13") (pin "3") (pinfunction "VSS1_3") (pintype "power_in"))
      (node (ref "J13") (pin "6") (pinfunction "VSS2_6") (pintype "power_in"))
      (node (ref "J13") (pin "COM") (pinfunction "COMMON_SW_COM") (pintype "passive"))
      (node (ref "J13") (pin "MT1") (pinfunction "GND_MT1") (pintype "power_in"))
      (node (ref "J14") (pin "6") (pinfunction "6_6") (pintype "passive"))
      (node (ref "J16") (pin "3") (pinfunction "1_3") (pintype "passive"))
      (node (ref "J17") (pin "5") (pinfunction "1_5") (pintype "passive"))
      (node (ref "J18") (pin "3") (pinfunction "1_3") (pintype "passive"))
      (node (ref "J20") (pin "2") (pinfunction "1_2") (pintype "passive"))
      (node (ref "J21") (pin "P$1") (pinfunction "GND_P$1") (pintype "bidirectional"))
      (node (ref "J21") (pin "P$2") (pinfunction "GND_P$2") (pintype "bidirectional"))
      (node (ref "J21") (pin "T-") (pinfunction "T-_T-") (pintype "bidirectional"))
      (node (ref "J4") (pin "5") (pinfunction "1_5") (pintype "passive"))
      (node (ref "J5") (pin "2") (pinfunction "2_2") (pintype "passive"))
      (node (ref "J6") (pin "6") (pinfunction "6_6") (pintype "passive"))
      (node (ref "J7") (pin "5") (pinfunction "1_5") (pintype "passive"))
      (node (ref "J9") (pin "3") (pinfunction "1_3") (pintype "passive"))
      (node (ref "LED3") (pin "C") (pinfunction "C_C") (pintype "passive"))
      (node (ref "LED4") (pin "C") (pinfunction "C_C") (pintype "passive"))
      (node (ref "LED5") (pin "C") (pinfunction "C_C") (pintype "passive"))
      (node (ref "R12") (pin "1") (pinfunction "1_1") (pintype "passive"))
      (node (ref "R20") (pin "1") (pinfunction "1_1") (pintype "passive"))
      (node (ref "R39") (pin "2") (pinfunction "2_2") (pintype "passive"))
      (node (ref "R41") (pin "2") (pinfunction "2_2") (pintype "passive"))
      (node (ref "R42") (pin "2") (pinfunction "2_2") (pintype "passive"))
      (node (ref "S1") (pin "1") (pinfunction "1_1") (pintype "passive"))
    )
    (net (code "39") (name "Net-(C2-Pad2)") (class "Default")
      (node (ref "C2") (pin "2") (pinfunction "2_2") (pintype "passive"))
      (node (ref "Q1") (pin "1") (pinfunction "1_1") (pintype "passive"))
      (node (ref "R11") (pin "2") (pinfunction "2_2") (pintype "passive"))
      (node (ref "R9") (pin "2") (pinfunction "2_2") (pintype "passive"))
    )
    (net (code "40") (name "Net-(C3-Pad1)") (class "Default")
      (node (ref "C3") (pin "1") (pinfunction "1_1") (pintype "passive"))
      (node (ref "J2") (pin "2") (pinfunction "2_2") (pintype "passive"))
    )
    (net (code "41") (name "Net-(C17-Pad1)") (class "Default")
      (node (ref "C17") (pin "1") (pinfunction "1_1") (pintype "passive"))
      (node (ref "R37") (pin "1") (pinfunction "1_1") (pintype "passive"))
      (node (ref "R38") (pin "2") (pinfunction "2_2") (pintype "passive"))
    )
    (net (code "42") (name "Net-(F1-Pad1)") (class "Default")
      (node (ref "F1") (pin "1") (pinfunction "1_1") (pintype "bidirectional"))
      (node (ref "J3") (pin "VBUS") (pinfunction "VBUS_VBUS") (pintype "bidirectional"))
    )
    (net (code "43") (name "Net-(IC1-(CTS)PD7)") (class "Default")
      (node (ref "IC1") (pin "13") (pinfunction "(CTS)PD7_13") (pintype "bidirectional"))
      (node (ref "J2") (pin "1") (pinfunction "1_1") (pintype "passive"))
    )
    (net (code "44") (name "Net-(IC1-(XCK)PD5)") (class "Default")
      (node (ref "IC1") (pin "11") (pinfunction "(XCK)PD5_11") (pintype "bidirectional"))
      (node (ref "R13") (pin "2") (pinfunction "2_2") (pintype "passive"))
    )
    (net (code "45") (name "Net-(IC1-D+)") (class "Default")
      (node (ref "IC1") (pin "29") (pinfunction "D+_29") (pintype "bidirectional"))
      (node (ref "R16") (pin "1") (pinfunction "1_1") (pintype "passive"))
    )
    (net (code "46") (name "Net-(IC1-D-)") (class "Default")
      (node (ref "IC1") (pin "30") (pinfunction "D-_30") (pintype "bidirectional"))
      (node (ref "R14") (pin "1") (pinfunction "1_1") (pintype "passive"))
    )
    (net (code "47") (name "Net-(IC1-PD4)") (class "Default")
      (node (ref "IC1") (pin "10") (pinfunction "PD4_10") (pintype "bidirectional"))
      (node (ref "R15") (pin "2") (pinfunction "2_2") (pintype "passive"))
    )
    (net (code "48") (name "Net-(IC1-UCAP)") (class "Default")
      (node (ref "C6") (pin "1") (pinfunction "1_1") (pintype "passive"))
      (node (ref "IC1") (pin "27") (pinfunction "UCAP_27") (pintype "passive"))
    )
    (net (code "49") (name "Net-(IC1-UGND)") (class "Default")
      (node (ref "IC1") (pin "28") (pinfunction "UGND_28") (pintype "power_in"))
      (node (ref "J3") (pin "GND") (pinfunction "GND_GND") (pintype "bidirectional"))
      (node (ref "J5") (pin "1") (pinfunction "1_1") (pintype "passive"))
      (node (ref "L1") (pin "2") (pinfunction "2_2") (pintype "passive"))
    )
    (net (code "50") (name "Net-(IC1-XTAL1)") (class "Default")
      (node (ref "IC1") (pin "1") (pinfunction "XTAL1_1") (pintype "bidirectional"))
      (node (ref "R11") (pin "1") (pinfunction "1_1") (pintype "passive"))
    )
    (net (code "51") (name "Net-(IC1-XTAL2)") (class "Default")
      (node (ref "C1") (pin "2") (pinfunction "2_2") (pintype "passive"))
      (node (ref "IC1") (pin "2") (pinfunction "XTAL2_2") (pintype "bidirectional"))
      (node (ref "Q1") (pin "3") (pinfunction "2_3") (pintype "passive"))
      (node (ref "R9") (pin "1") (pinfunction "1_1") (pintype "passive"))
    )
    (net (code "52") (name "Net-(IC2-DIN{slash}~{CONFIG})") (class "Default")
      (node (ref "IC2") (pin "3") (pinfunction "DIN/~{CONFIG}_3") (pintype "input"))
      (node (ref "R10") (pin "1") (pinfunction "1_1") (pintype "passive"))
      (node (ref "R12") (pin "2") (pinfunction "2_2") (pintype "passive"))
    )
    (net (code "53") (name "Net-(IC3-COMP)") (class "Default")
      (node (ref "IC3") (pin "5") (pinfunction "COMP_5") (pintype "bidirectional"))
      (node (ref "R20") (pin "2") (pinfunction "2_2") (pintype "passive"))
      (node (ref "R21") (pin "1") (pinfunction "1_1") (pintype "passive"))
    )
    (net (code "54") (name "Net-(IC3-DVR)") (class "Default")
      (node (ref "IC3") (pin "1") (pinfunction "SWC_1") (pintype "bidirectional"))
      (node (ref "IC3") (pin "7") (pinfunction "SEN_7") (pintype "bidirectional"))
      (node (ref "IC3") (pin "8") (pinfunction "DVR_8") (pintype "bidirectional"))
      (node (ref "R18") (pin "2") (pinfunction "2_2") (pintype "passive"))
    )
    (net (code "55") (name "Net-(IC3-SWE)") (class "Default")
      (node (ref "D1") (pin "C") (pinfunction "C_C") (pintype "passive"))
      (node (ref "IC3") (pin "2") (pinfunction "SWE_2") (pintype "bidirectional"))
      (node (ref "L2") (pin "P$1") (pinfunction "1_P$1") (pintype "passive"))
    )
    (net (code "56") (name "Net-(IC3-TC)") (class "Default")
      (node (ref "C11") (pin "1") (pinfunction "1_1") (pintype "passive"))
      (node (ref "IC3") (pin "3") (pinfunction "TC_3") (pintype "bidirectional"))
    )
    (net (code "57") (name "Net-(IC4A-O)") (class "Default")
      (node (ref "IC4") (pin "4") (pinfunction "O_4") (pintype "output"))
      (node (ref "R23") (pin "2") (pinfunction "2_2") (pintype "passive"))
    )
    (net (code "58") (name "Net-(IC5A-O)") (class "Default")
      (node (ref "IC5") (pin "4") (pinfunction "O_4") (pintype "output"))
      (node (ref "R22") (pin "2") (pinfunction "2_2") (pintype "passive"))
    )
    (net (code "59") (name "Net-(IC6-(SCL{slash}INT0)PD0)") (class "Default")
      (node (ref "IC6") (pin "43") (pinfunction "(SCL/INT0)PD0_43") (pintype "bidirectional"))
      (node (ref "J12") (pin "2") (pinfunction "2_2") (pintype "passive"))
    )
    (net (code "60") (name "Net-(IC6-(SDA{slash}INT1)PD1)") (class "Default")
      (node (ref "IC6") (pin "44") (pinfunction "(SDA/INT1)PD1_44") (pintype "bidirectional"))
      (node (ref "J12") (pin "1") (pinfunction "1_1") (pintype "passive"))
    )
    (net (code "61") (name "Net-(IC6-AREF)") (class "Default")
      (node (ref "C13") (pin "2") (pinfunction "2_2") (pintype "passive"))
      (node (ref "IC6") (pin "98") (pinfunction "AREF_98") (pintype "bidirectional"))
    )
    (net (code "62") (name "Net-(IC6-PJ0(RXD3{slash}PCINT9))") (class "Default")
      (node (ref "IC6") (pin "63") (pinfunction "PJ0(RXD3/PCINT9)_63") (pintype "bidirectional"))
      (node (ref "J15") (pin "1") (pinfunction "1_1") (pintype "passive"))
    )
    (net (code "63") (name "Net-(IC6-PJ1(TXD3{slash}PCINT10))") (class "Default")
      (node (ref "IC6") (pin "64") (pinfunction "PJ1(TXD3/PCINT10)_64") (pintype "bidirectional"))
      (node (ref "J15") (pin "2") (pinfunction "2_2") (pintype "passive"))
    )
    (net (code "64") (name "Net-(IC6-XTAL1)") (class "Default")
      (node (ref "C8") (pin "2") (pinfunction "2_2") (pintype "passive"))
      (node (ref "IC6") (pin "34") (pinfunction "XTAL1_34") (pintype "input"))
      (node (ref "Q2") (pin "1") (pinfunction "1_1") (pintype "passive"))
    )
    (net (code "65") (name "Net-(IC6-XTAL2)") (class "Default")
      (node (ref "C7") (pin "2") (pinfunction "2_2") (pintype "passive"))
      (node (ref "IC6") (pin "33") (pinfunction "XTAL2_33") (pintype "output"))
      (node (ref "Q2") (pin "3") (pinfunction "2_3") (pintype "passive"))
    )
    (net (code "66") (name "Net-(IC7A-O)") (class "Default")
      (node (ref "IC7") (pin "2") (pinfunction "O_2") (pintype "output"))
      (node (ref "J13") (pin "2") (pinfunction "DATA_IN_2") (pintype "input"))
    )
    (net (code "67") (name "Net-(IC7B-O)") (class "Default")
      (node (ref "IC7") (pin "4") (pinfunction "O_4") (pintype "output"))
      (node (ref "J13") (pin "5") (pinfunction "SCLK_5") (pintype "input"))
    )
    (net (code "68") (name "Net-(IC7C-O)") (class "Default")
      (node (ref "IC7") (pin "6") (pinfunction "O_6") (pintype "output"))
      (node (ref "J13") (pin "1") (pinfunction "CS_1") (pintype "input"))
      (node (ref "LED6") (pin "C") (pinfunction "C_C") (pintype "passive"))
    )
    (net (code "69") (name "Net-(IC7D-O)") (class "Default")
      (node (ref "IC7") (pin "10") (pinfunction "O_10") (pintype "output"))
      (node (ref "R26") (pin "1") (pinfunction "1_1") (pintype "passive"))
    )
    (net (code "70") (name "Net-(IC9-+IN)") (class "Default")
      (node (ref "C18") (pin "1") (pinfunction "1_1") (pintype "passive"))
      (node (ref "IC9") (pin "3") (pinfunction "+IN_3") (pintype "input"))
      (node (ref "R38") (pin "1") (pinfunction "1_1") (pintype "passive"))
    )
    (net (code "71") (name "Net-(IC10A--IN)") (class "Default")
      (node (ref "IC10") (pin "2") (pinfunction "-IN_2") (pintype "input"))
      (node (ref "R30") (pin "2") (pinfunction "2_2") (pintype "passive"))
      (node (ref "R41") (pin "1") (pinfunction "1_1") (pintype "passive"))
    )
    (net (code "72") (name "Net-(IC11A-I0)") (class "Default")
      (node (ref "IC11") (pin "1") (pinfunction "I0_1") (pintype "input"))
      (node (ref "IC11") (pin "2") (pinfunction "I1_2") (pintype "input"))
      (node (ref "IC13") (pin "1") (pinfunction "I0_1") (pintype "input"))
      (node (ref "IC13") (pin "2") (pinfunction "I1_2") (pintype "input"))
      (node (ref "R42") (pin "1") (pinfunction "1_1") (pintype "passive"))
      (node (ref "S2") (pin "1") (pinfunction "1_1") (pintype "passive"))
    )
    (net (code "73") (name "Net-(IC14-T+)") (class "Default")
      (node (ref "IC14") (pin "3") (pinfunction "T+_3") (pintype "bidirectional"))
      (node (ref "J21") (pin "T+") (pinfunction "T+_T+") (pintype "bidirectional"))
    )
    (net (code "74") (name "Net-(J1D-1)") (class "Default")
      (node (ref "J1") (pin "4") (pinfunction "1_4") (pintype "passive"))
      (node (ref "J4") (pin "4") (pinfunction "1_4") (pintype "passive"))
      (node (ref "J7") (pin "4") (pinfunction "1_4") (pintype "passive"))
      (node (ref "J8") (pin "1") (pinfunction "P_1") (pintype "passive"))
      (node (ref "R3") (pin "1") (pinfunction "1_1") (pintype "passive"))
    )
    (net (code "75") (name "Net-(J3-SH$1)") (class "Default")
      (node (ref "J3") (pin "SH1") (pinfunction "SH$1_SH1") (pintype "passive"))
      (node (ref "J3") (pin "SH2") (pinfunction "SH$2_SH2") (pintype "passive"))
      (node (ref "J3") (pin "SH3") (pinfunction "SH$3_SH3") (pintype "passive"))
      (node (ref "J3") (pin "SH4") (pinfunction "SH$4_SH4") (pintype "passive"))
      (node (ref "L1") (pin "1") (pinfunction "1_1") (pintype "passive"))
      (node (ref "Z1") (pin "3") (pinfunction "P$3_3") (pintype "bidirectional"))
    )
    (net (code "76") (name "Net-(J17C-1)") (class "Default")
      (node (ref "J17") (pin "3") (pinfunction "1_3") (pintype "passive"))
      (node (ref "R34") (pin "2") (pinfunction "2_2") (pintype "passive"))
    )
    (net (code "77") (name "Net-(J19B-1)") (class "Default")
      (node (ref "J19") (pin "2") (pinfunction "1_2") (pintype "passive"))
      (node (ref "J20") (pin "1") (pinfunction "1_1") (pintype "passive"))
    )
    (net (code "78") (name "Net-(LED1-PadC)") (class "Default")
      (node (ref "LED1") (pin "C") (pinfunction "C_C") (pintype "passive"))
      (node (ref "R13") (pin "1") (pinfunction "1_1") (pintype "passive"))
    )
    (net (code "79") (name "Net-(LED2-PadC)") (class "Default")
      (node (ref "LED2") (pin "C") (pinfunction "C_C") (pintype "passive"))
      (node (ref "R15") (pin "1") (pinfunction "1_1") (pintype "passive"))
    )
    (net (code "80") (name "Net-(LED3-PadA)") (class "Default")
      (node (ref "LED3") (pin "A") (pinfunction "A_A") (pintype "passive"))
      (node (ref "R19") (pin "2") (pinfunction "2_2") (pintype "passive"))
    )
    (net (code "81") (name "Net-(LED4-PadA)") (class "Default")
      (node (ref "LED4") (pin "A") (pinfunction "A_A") (pintype "passive"))
      (node (ref "R22") (pin "1") (pinfunction "1_1") (pintype "passive"))
    )
    (net (code "82") (name "Net-(LED5-PadA)") (class "Default")
      (node (ref "LED5") (pin "A") (pinfunction "A_A") (pintype "passive"))
      (node (ref "R23") (pin "1") (pinfunction "1_1") (pintype "passive"))
    )
    (net (code "83") (name "Net-(LED6-PadA)") (class "Default")
      (node (ref "LED6") (pin "A") (pinfunction "A_A") (pintype "passive"))
      (node (ref "R26") (pin "2") (pinfunction "2_2") (pintype "passive"))
    )
    (net (code "84") (name "Net-(LED7-PadA)") (class "Default")
      (node (ref "LED7") (pin "A") (pinfunction "A_A") (pintype "passive"))
      (node (ref "R27") (pin "1") (pinfunction "1_1") (pintype "passive"))
    )
    (net (code "85") (name "Net-(LED8-PadA)") (class "Default")
      (node (ref "LED8") (pin "A") (pinfunction "A_A") (pintype "passive"))
      (node (ref "R36") (pin "2") (pinfunction "2_2") (pintype "passive"))
    )
    (net (code "86") (name "Net-(LED9-PadA)") (class "Default")
      (node (ref "LED9") (pin "A") (pinfunction "A_A") (pintype "passive"))
      (node (ref "R33") (pin "1") (pinfunction "1_1") (pintype "passive"))
    )
    (net (code "87") (name "Net-(Z1-P$1)") (class "Default")
      (node (ref "J3") (pin "D-") (pinfunction "D-_D-") (pintype "bidirectional"))
      (node (ref "R14") (pin "2") (pinfunction "2_2") (pintype "passive"))
      (node (ref "Z1") (pin "1") (pinfunction "P$1_1") (pintype "bidirectional"))
    )
    (net (code "88") (name "Net-(Z1-P$2)") (class "Default")
      (node (ref "J3") (pin "D+") (pinfunction "D+_D+") (pintype "bidirectional"))
      (node (ref "R16") (pin "2") (pinfunction "2_2") (pintype "passive"))
      (node (ref "Z1") (pin "2") (pinfunction "P$2_2") (pintype "bidirectional"))
    )
    (net (code "89") (name "unconnected-(IC1-(RTS)PD6-Pad12)") (class "Default")
      (node (ref "IC1") (pin "12") (pinfunction "(RTS)PD6_12") (pintype "bidirectional"))
    )
    (net (code "90") (name "unconnected-(IC1-(SS)PB0-Pad14)") (class "Default")
      (node (ref "IC1") (pin "14") (pinfunction "(SS)PB0_14") (pintype "bidirectional"))
    )
    (net (code "91") (name "unconnected-(IC1-PB4-Pad18)") (class "Default")
      (node (ref "IC1") (pin "18") (pinfunction "PB4_18") (pintype "bidirectional"))
    )
    (net (code "92") (name "unconnected-(IC1-PB5-Pad19)") (class "Default")
      (node (ref "IC1") (pin "19") (pinfunction "PB5_19") (pintype "bidirectional"))
    )
    (net (code "93") (name "unconnected-(IC1-PB6-Pad20)") (class "Default")
      (node (ref "IC1") (pin "20") (pinfunction "PB6_20") (pintype "bidirectional"))
    )
    (net (code "94") (name "unconnected-(IC1-PB7-Pad21)") (class "Default")
      (node (ref "IC1") (pin "21") (pinfunction "PB7_21") (pintype "bidirectional"))
    )
    (net (code "95") (name "unconnected-(IC1-PC2-Pad5)") (class "Default")
      (node (ref "IC1") (pin "5") (pinfunction "PC2_5") (pintype "bidirectional"))
    )
    (net (code "96") (name "unconnected-(IC1-PC4-Pad26)") (class "Default")
      (node (ref "IC1") (pin "26") (pinfunction "PC4_26") (pintype "bidirectional"))
    )
    (net (code "97") (name "unconnected-(IC1-PC5-Pad25)") (class "Default")
      (node (ref "IC1") (pin "25") (pinfunction "PC5_25") (pintype "bidirectional"))
    )
    (net (code "98") (name "unconnected-(IC1-PC6-Pad23)") (class "Default")
      (node (ref "IC1") (pin "23") (pinfunction "PC6_23") (pintype "bidirectional"))
    )
    (net (code "99") (name "unconnected-(IC1-PC7-Pad22)") (class "Default")
      (node (ref "IC1") (pin "22") (pinfunction "PC7_22") (pintype "bidirectional"))
    )
    (net (code "100") (name "unconnected-(IC1-PD0-Pad6)") (class "Default")
      (node (ref "IC1") (pin "6") (pinfunction "PD0_6") (pintype "bidirectional"))
    )
    (net (code "101") (name "unconnected-(IC1-PD1-Pad7)") (class "Default")
      (node (ref "IC1") (pin "7") (pinfunction "PD1_7") (pintype "bidirectional"))
    )
    (net (code "102") (name "unconnected-(IC2-AD0{slash}DIO0-Pad20)") (class "Default")
      (node (ref "IC2") (pin "20") (pinfunction "AD0/DIO0_20") (pintype "bidirectional"))
    )
    (net (code "103") (name "unconnected-(IC2-AD1{slash}DIO1-Pad19)") (class "Default")
      (node (ref "IC2") (pin "19") (pinfunction "AD1/DIO1_19") (pintype "bidirectional"))
    )
    (net (code "104") (name "unconnected-(IC2-AD2{slash}DIO2-Pad18)") (class "Default")
      (node (ref "IC2") (pin "18") (pinfunction "AD2/DIO2_18") (pintype "bidirectional"))
    )
    (net (code "105") (name "unconnected-(IC2-ASSOC{slash}AD5{slash}DIO5-Pad15)") (class "Default")
      (node (ref "IC2") (pin "15") (pinfunction "ASSOC/AD5/DIO5_15") (pintype "bidirectional"))
    )
    (net (code "106") (name "unconnected-(IC2-CD{slash}DOUT_EN{slash}DO8-Pad4)") (class "Default")
      (node (ref "IC2") (pin "4") (pinfunction "CD/DOUT_EN/DO8_4") (pintype "output"))
    )
    (net (code "107") (name "unconnected-(IC2-COORD_SEL{slash}AD3{slash}DIO3-Pad17)") (class "Default")
      (node (ref "IC2") (pin "17") (pinfunction "COORD_SEL/AD3/DIO3_17") (pintype "bidirectional"))
    )
    (net (code "108") (name "unconnected-(IC2-ON{slash}~{SLEEP}-Pad13)") (class "Default")
      (node (ref "IC2") (pin "13") (pinfunction "ON/~{SLEEP}_13") (pintype "output"))
    )
    (net (code "109") (name "unconnected-(IC2-PWM0{slash}RSSI-Pad6)") (class "Default")
      (node (ref "IC2") (pin "6") (pinfunction "PWM0/RSSI_6") (pintype "output"))
    )
    (net (code "110") (name "unconnected-(IC2-RF_TX{slash}AD4{slash}DIO4-Pad11)") (class "Default")
      (node (ref "IC2") (pin "11") (pinfunction "RF_TX/AD4/DIO4_11") (pintype "bidirectional"))
    )
    (net (code "111") (name "unconnected-(IC2-VREF-Pad14)") (class "Default")
      (node (ref "IC2") (pin "14") (pinfunction "VREF_14") (pintype "input"))
    )
    (net (code "112") (name "unconnected-(IC2-~{CTS}{slash}DIO7-Pad12)") (class "Default")
      (node (ref "IC2") (pin "12") (pinfunction "~{CTS}/DIO7_12") (pintype "bidirectional"))
    )
    (net (code "113") (name "unconnected-(IC2-~{DTR}{slash}SLEEP_RQ{slash}DI8-Pad9)") (class "Default")
      (node (ref "IC2") (pin "9") (pinfunction "~{DTR}/SLEEP_RQ/DI8_9") (pintype "bidirectional"))
    )
    (net (code "114") (name "unconnected-(IC2-~{RESET}-Pad5)") (class "Default")
      (node (ref "IC2") (pin "5") (pinfunction "~{RESET}_5") (pintype "input"))
    )
    (net (code "115") (name "unconnected-(IC2-~{RTS}{slash}AD6{slash}DIO6-Pad16)") (class "Default")
      (node (ref "IC2") (pin "16") (pinfunction "~{RTS}/AD6/DIO6_16") (pintype "bidirectional"))
    )
    (net (code "116") (name "unconnected-(IC6-(A8)PC0-Pad53)") (class "Default")
      (node (ref "IC6") (pin "53") (pinfunction "(A8)PC0_53") (pintype "bidirectional"))
    )
    (net (code "117") (name "unconnected-(IC6-(A9)PC1-Pad54)") (class "Default")
      (node (ref "IC6") (pin "54") (pinfunction "(A9)PC1_54") (pintype "bidirectional"))
    )
    (net (code "118") (name "unconnected-(IC6-(A10)PC2-Pad55)") (class "Default")
      (node (ref "IC6") (pin "55") (pinfunction "(A10)PC2_55") (pintype "bidirectional"))
    )
    (net (code "119") (name "unconnected-(IC6-(A11)PC3-Pad56)") (class "Default")
      (node (ref "IC6") (pin "56") (pinfunction "(A11)PC3_56") (pintype "bidirectional"))
    )
    (net (code "120") (name "unconnected-(IC6-(A12)PC4-Pad57)") (class "Default")
      (node (ref "IC6") (pin "57") (pinfunction "(A12)PC4_57") (pintype "bidirectional"))
    )
    (net (code "121") (name "unconnected-(IC6-(A13)PC5-Pad58)") (class "Default")
      (node (ref "IC6") (pin "58") (pinfunction "(A13)PC5_58") (pintype "bidirectional"))
    )
    (net (code "122") (name "unconnected-(IC6-(A14)PC6-Pad59)") (class "Default")
      (node (ref "IC6") (pin "59") (pinfunction "(A14)PC6_59") (pintype "bidirectional"))
    )
    (net (code "123") (name "unconnected-(IC6-(A15)PC7-Pad60)") (class "Default")
      (node (ref "IC6") (pin "60") (pinfunction "(A15)PC7_60") (pintype "bidirectional"))
    )
    (net (code "124") (name "unconnected-(IC6-(AD0)PA0-Pad78)") (class "Default")
      (node (ref "IC6") (pin "78") (pinfunction "(AD0)PA0_78") (pintype "bidirectional"))
    )
    (net (code "125") (name "unconnected-(IC6-(AD1)PA1-Pad77)") (class "Default")
      (node (ref "IC6") (pin "77") (pinfunction "(AD1)PA1_77") (pintype "bidirectional"))
    )
    (net (code "126") (name "unconnected-(IC6-(AD2)PA2-Pad76)") (class "Default")
      (node (ref "IC6") (pin "76") (pinfunction "(AD2)PA2_76") (pintype "bidirectional"))
    )
    (net (code "127") (name "unconnected-(IC6-(AD3)PA3-Pad75)") (class "Default")
      (node (ref "IC6") (pin "75") (pinfunction "(AD3)PA3_75") (pintype "bidirectional"))
    )
    (net (code "128") (name "unconnected-(IC6-(AD4)PA4-Pad74)") (class "Default")
      (node (ref "IC6") (pin "74") (pinfunction "(AD4)PA4_74") (pintype "bidirectional"))
    )
    (net (code "129") (name "unconnected-(IC6-(AD5)PA5-Pad73)") (class "Default")
      (node (ref "IC6") (pin "73") (pinfunction "(AD5)PA5_73") (pintype "bidirectional"))
    )
    (net (code "130") (name "unconnected-(IC6-(AD6)PA6-Pad72)") (class "Default")
      (node (ref "IC6") (pin "72") (pinfunction "(AD6)PA6_72") (pintype "bidirectional"))
    )
    (net (code "131") (name "unconnected-(IC6-(AD7)PA7-Pad71)") (class "Default")
      (node (ref "IC6") (pin "71") (pinfunction "(AD7)PA7_71") (pintype "bidirectional"))
    )
    (net (code "132") (name "unconnected-(IC6-(ADC0)PF0-Pad97)") (class "Default")
      (node (ref "IC6") (pin "97") (pinfunction "(ADC0)PF0_97") (pintype "bidirectional"))
    )
    (net (code "133") (name "unconnected-(IC6-(ADC2)PF2-Pad95)") (class "Default")
      (node (ref "IC6") (pin "95") (pinfunction "(ADC2)PF2_95") (pintype "bidirectional"))
    )
    (net (code "134") (name "unconnected-(IC6-(ADC6{slash}TDO)PF6-Pad91)") (class "Default")
      (node (ref "IC6") (pin "91") (pinfunction "(ADC6/TDO)PF6_91") (pintype "bidirectional"))
    )
    (net (code "135") (name "unconnected-(IC6-(ADC7{slash}TDI)PF7-Pad90)") (class "Default")
      (node (ref "IC6") (pin "90") (pinfunction "(ADC7/TDI)PF7_90") (pintype "bidirectional"))
    )
    (net (code "136") (name "unconnected-(IC6-(ALE)PG2-Pad70)") (class "Default")
      (node (ref "IC6") (pin "70") (pinfunction "(ALE)PG2_70") (pintype "bidirectional"))
    )
    (net (code "137") (name "unconnected-(IC6-(CLKO{slash}ICP3{slash}INT7)PE7-Pad9)") (class "Default")
      (node (ref "IC6") (pin "9") (pinfunction "(CLKO/ICP3/INT7)PE7_9") (pintype "bidirectional"))
    )
    (net (code "138") (name "unconnected-(IC6-(OC0A{slash}OC1C{slash}PCINT7)PB7-Pad26)") (class "Default")
      (node (ref "IC6") (pin "26") (pinfunction "(OC0A/OC1C/PCINT7)PB7_26") (pintype "bidirectional"))
    )
    (net (code "139") (name "unconnected-(IC6-(RD)PG1-Pad52)") (class "Default")
      (node (ref "IC6") (pin "52") (pinfunction "(RD)PG1_52") (pintype "bidirectional"))
    )
    (net (code "140") (name "unconnected-(IC6-(SS{slash}PCINT0)PB0-Pad19)") (class "Default")
      (node (ref "IC6") (pin "19") (pinfunction "(SS/PCINT0)PB0_19") (pintype "bidirectional"))
    )
    (net (code "141") (name "unconnected-(IC6-(T0)PD7-Pad50)") (class "Default")
      (node (ref "IC6") (pin "50") (pinfunction "(T0)PD7_50") (pintype "bidirectional"))
    )
    (net (code "142") (name "unconnected-(IC6-(T1)PD6-Pad49)") (class "Default")
      (node (ref "IC6") (pin "49") (pinfunction "(T1)PD6_49") (pintype "bidirectional"))
    )
    (net (code "143") (name "unconnected-(IC6-(T3{slash}INT6)PE6-Pad8)") (class "Default")
      (node (ref "IC6") (pin "8") (pinfunction "(T3/INT6)PE6_8") (pintype "bidirectional"))
    )
    (net (code "144") (name "unconnected-(IC6-(TOSC1)PG4-Pad29)") (class "Default")
      (node (ref "IC6") (pin "29") (pinfunction "(TOSC1)PG4_29") (pintype "bidirectional"))
    )
    (net (code "145") (name "unconnected-(IC6-(TOSC2)PG3-Pad28)") (class "Default")
      (node (ref "IC6") (pin "28") (pinfunction "(TOSC2)PG3_28") (pintype "bidirectional"))
    )
    (net (code "146") (name "unconnected-(IC6-(WR)PG0-Pad51)") (class "Default")
      (node (ref "IC6") (pin "51") (pinfunction "(WR)PG0_51") (pintype "bidirectional"))
    )
    (net (code "147") (name "unconnected-(IC6-(XCK0{slash}AIN0)PE2-Pad4)") (class "Default")
      (node (ref "IC6") (pin "4") (pinfunction "(XCK0/AIN0)PE2_4") (pintype "bidirectional"))
    )
    (net (code "148") (name "unconnected-(IC6-(XCK1)PD5-Pad48)") (class "Default")
      (node (ref "IC6") (pin "48") (pinfunction "(XCK1)PD5_48") (pintype "bidirectional"))
    )
    (net (code "149") (name "unconnected-(IC6-PH2(XCK2)-Pad14)") (class "Default")
      (node (ref "IC6") (pin "14") (pinfunction "PH2(XCK2)_14") (pintype "bidirectional"))
    )
    (net (code "150") (name "unconnected-(IC6-PH7(T4)-Pad27)") (class "Default")
      (node (ref "IC6") (pin "27") (pinfunction "PH7(T4)_27") (pintype "bidirectional"))
    )
    (net (code "151") (name "unconnected-(IC6-PJ2(XCK3{slash}PCINT11)-Pad65)") (class "Default")
      (node (ref "IC6") (pin "65") (pinfunction "PJ2(XCK3/PCINT11)_65") (pintype "bidirectional"))
    )
    (net (code "152") (name "unconnected-(IC6-PJ3(PCINT12)-Pad66)") (class "Default")
      (node (ref "IC6") (pin "66") (pinfunction "PJ3(PCINT12)_66") (pintype "bidirectional"))
    )
    (net (code "153") (name "unconnected-(IC6-PJ4(PCINT13)-Pad67)") (class "Default")
      (node (ref "IC6") (pin "67") (pinfunction "PJ4(PCINT13)_67") (pintype "bidirectional"))
    )
    (net (code "154") (name "unconnected-(IC6-PJ5(PCINT14)-Pad68)") (class "Default")
      (node (ref "IC6") (pin "68") (pinfunction "PJ5(PCINT14)_68") (pintype "bidirectional"))
    )
    (net (code "155") (name "unconnected-(IC6-PJ6(PCINT15)-Pad69)") (class "Default")
      (node (ref "IC6") (pin "69") (pinfunction "PJ6(PCINT15)_69") (pintype "bidirectional"))
    )
    (net (code "156") (name "unconnected-(IC6-PJ7-Pad79)") (class "Default")
      (node (ref "IC6") (pin "79") (pinfunction "PJ7_79") (pintype "bidirectional"))
    )
    (net (code "157") (name "unconnected-(IC6-PK0(ADC8{slash}PCINT16)-Pad89)") (class "Default")
      (node (ref "IC6") (pin "89") (pinfunction "PK0(ADC8/PCINT16)_89") (pintype "bidirectional"))
    )
    (net (code "158") (name "unconnected-(IC6-PK1(ADC9{slash}PCINT17)-Pad88)") (class "Default")
      (node (ref "IC6") (pin "88") (pinfunction "PK1(ADC9/PCINT17)_88") (pintype "bidirectional"))
    )
    (net (code "159") (name "unconnected-(IC6-PK2(ADC10{slash}PCINT18)-Pad87)") (class "Default")
      (node (ref "IC6") (pin "87") (pinfunction "PK2(ADC10/PCINT18)_87") (pintype "bidirectional"))
    )
    (net (code "160") (name "unconnected-(IC6-PK3(ADC11{slash}PCINT19)-Pad86)") (class "Default")
      (node (ref "IC6") (pin "86") (pinfunction "PK3(ADC11/PCINT19)_86") (pintype "bidirectional"))
    )
    (net (code "161") (name "unconnected-(IC6-PK4(ADC12{slash}PCINT20)-Pad85)") (class "Default")
      (node (ref "IC6") (pin "85") (pinfunction "PK4(ADC12/PCINT20)_85") (pintype "bidirectional"))
    )
    (net (code "162") (name "unconnected-(IC6-PK5(ADC13{slash}PCINT21)-Pad84)") (class "Default")
      (node (ref "IC6") (pin "84") (pinfunction "PK5(ADC13/PCINT21)_84") (pintype "bidirectional"))
    )
    (net (code "163") (name "unconnected-(IC6-PK6(ADC14{slash}PCINT22)-Pad83)") (class "Default")
      (node (ref "IC6") (pin "83") (pinfunction "PK6(ADC14/PCINT22)_83") (pintype "bidirectional"))
    )
    (net (code "164") (name "unconnected-(IC6-PK7(ADC15{slash}PCINT23)-Pad82)") (class "Default")
      (node (ref "IC6") (pin "82") (pinfunction "PK7(ADC15/PCINT23)_82") (pintype "bidirectional"))
    )
    (net (code "165") (name "unconnected-(IC6-PL0(ICP4)-Pad35)") (class "Default")
      (node (ref "IC6") (pin "35") (pinfunction "PL0(ICP4)_35") (pintype "bidirectional"))
    )
    (net (code "166") (name "unconnected-(IC6-PL1(ICP5)-Pad36)") (class "Default")
      (node (ref "IC6") (pin "36") (pinfunction "PL1(ICP5)_36") (pintype "bidirectional"))
    )
    (net (code "167") (name "unconnected-(IC6-PL2(T5)-Pad37)") (class "Default")
      (node (ref "IC6") (pin "37") (pinfunction "PL2(T5)_37") (pintype "bidirectional"))
    )
    (net (code "168") (name "unconnected-(IC6-PL3(OC5A)-Pad38)") (class "Default")
      (node (ref "IC6") (pin "38") (pinfunction "PL3(OC5A)_38") (pintype "bidirectional"))
    )
    (net (code "169") (name "unconnected-(IC6-PL4(OC5B)-Pad39)") (class "Default")
      (node (ref "IC6") (pin "39") (pinfunction "PL4(OC5B)_39") (pintype "bidirectional"))
    )
    (net (code "170") (name "unconnected-(IC6-PL5(OC5C)-Pad40)") (class "Default")
      (node (ref "IC6") (pin "40") (pinfunction "PL5(OC5C)_40") (pintype "bidirectional"))
    )
    (net (code "171") (name "unconnected-(IC6-PL6-Pad41)") (class "Default")
      (node (ref "IC6") (pin "41") (pinfunction "PL6_41") (pintype "bidirectional"))
    )
    (net (code "172") (name "unconnected-(IC6-PL7-Pad42)") (class "Default")
      (node (ref "IC6") (pin "42") (pinfunction "PL7_42") (pintype "bidirectional"))
    )
    (net (code "173") (name "unconnected-(IC7E-O-Pad12)") (class "Default")
      (node (ref "IC7") (pin "12") (pinfunction "O_12") (pintype "output"))
    )
    (net (code "174") (name "unconnected-(IC7F-O-Pad15)") (class "Default")
      (node (ref "IC7") (pin "15") (pinfunction "O_15") (pintype "output"))
    )
    (net (code "175") (name "unconnected-(IC10B-OUT-Pad7)") (class "Default")
      (node (ref "IC10") (pin "7") (pinfunction "OUT_7") (pintype "output"))
    )
    (net (code "176") (name "unconnected-(IC14-NC-Pad8)") (class "Default")
      (node (ref "IC14") (pin "8") (pinfunction "NC_8") (pintype "no_connect"))
    )
    (net (code "177") (name "unconnected-(J3-PadID)") (class "Default")
      (node (ref "J3") (pin "ID") (pinfunction "ID_ID") (pintype "bidirectional"))
    )
    (net (code "178") (name "unconnected-(J13-DAT1-Pad8)") (class "Default")
      (node (ref "J13") (pin "8") (pinfunction "DAT1_8") (pintype "bidirectional"))
    )
    (net (code "179") (name "unconnected-(J13-DAT2-Pad9)") (class "Default")
      (node (ref "J13") (pin "9") (pinfunction "DAT2_9") (pintype "bidirectional"))
    )
    (net (code "180") (name "unconnected-(J13-WRITE_PROTECT-PadWP)") (class "Default")
      (node (ref "J13") (pin "WP") (pinfunction "WRITE_PROTECT_WP") (pintype "passive"))
    )
  )
)
